# tester.net
KiCad netlist of a schematic drawn in EAGLE
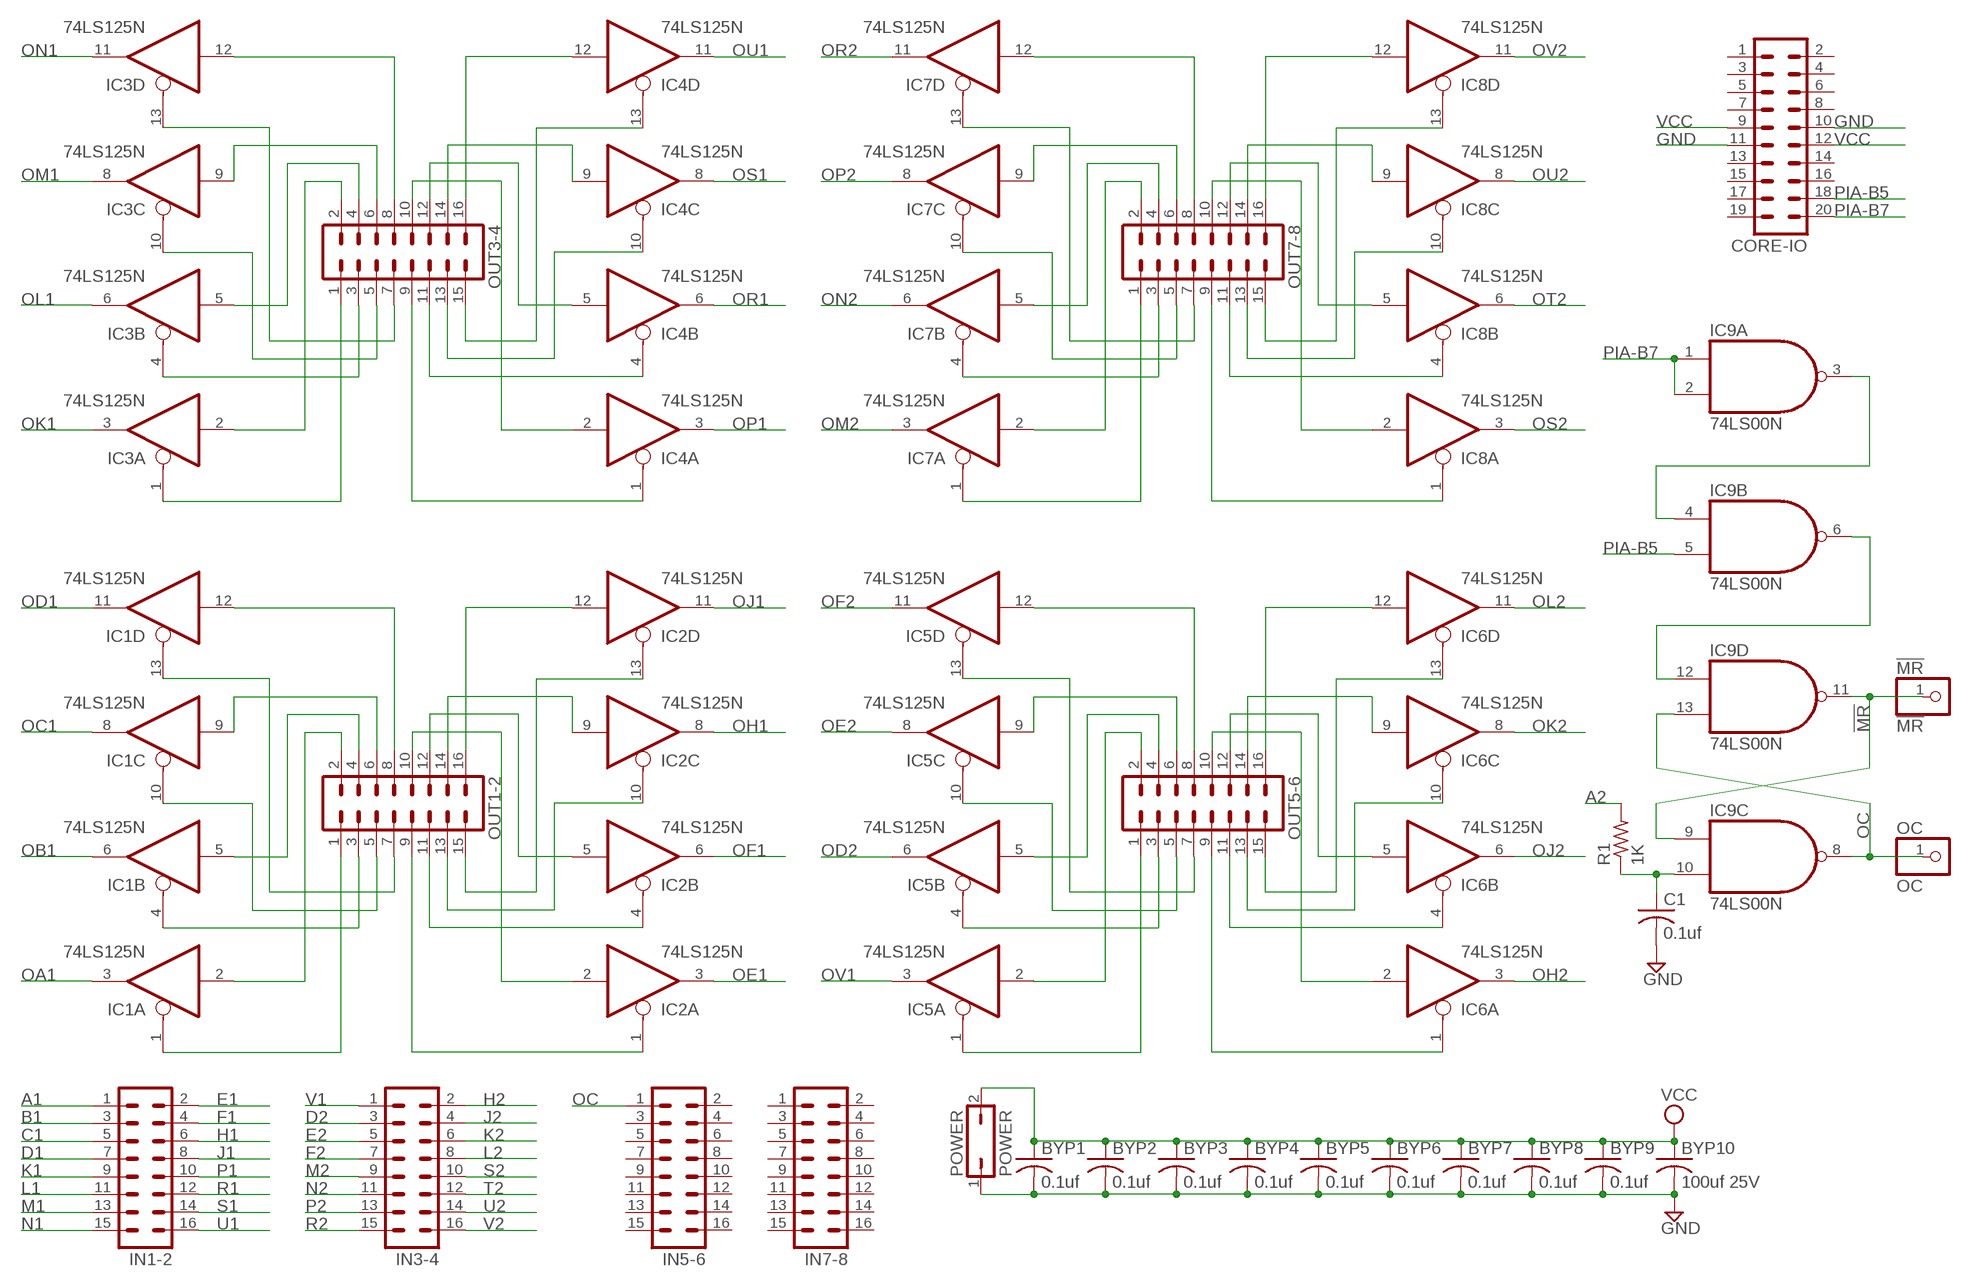
[diagram p0: schematic, sheet 1]
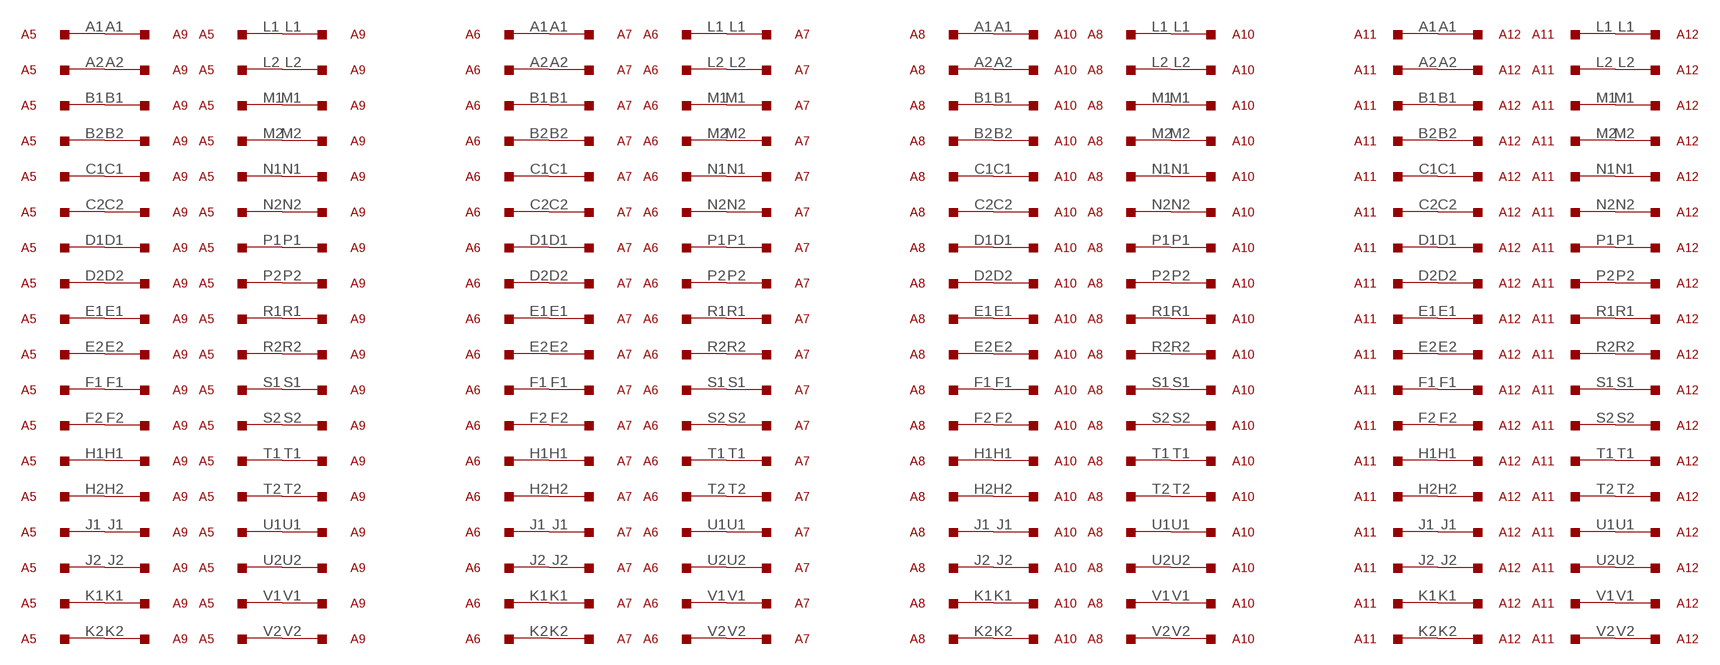
[diagram p1: schematic, sheet 2]
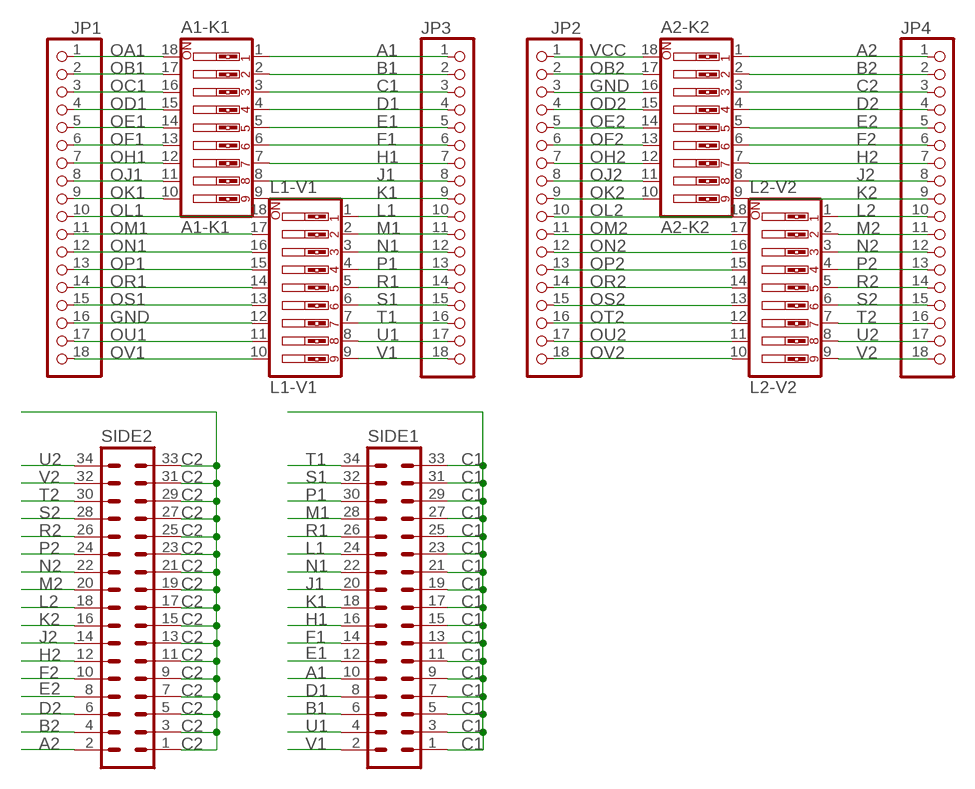
[diagram p2: schematic, sheet 3]

(export (version "E")
  (design (tool "Eeschema 10.0.6"))
  (components
    (comp (ref "A5")
      (value "M916")
      (footprint "eagle-import:H807")
      (libsource (lib "eagle-import") (part "M916"))
    )
    (comp (ref "A6")
      (value "M916")
      (footprint "eagle-import:H807")
      (libsource (lib "eagle-import") (part "M916"))
    )
    (comp (ref "A7")
      (value "M916")
      (footprint "eagle-import:H807")
      (libsource (lib "eagle-import") (part "M916"))
    )
    (comp (ref "A8")
      (value "M916")
      (footprint "eagle-import:H807")
      (libsource (lib "eagle-import") (part "M916"))
    )
    (comp (ref "A9")
      (value "M916")
      (footprint "eagle-import:H807")
      (libsource (lib "eagle-import") (part "M916"))
    )
    (comp (ref "A10")
      (value "M916")
      (footprint "eagle-import:H807")
      (libsource (lib "eagle-import") (part "M916"))
    )
    (comp (ref "A11")
      (value "M916")
      (footprint "eagle-import:H807")
      (libsource (lib "eagle-import") (part "M916"))
    )
    (comp (ref "A12")
      (value "M916")
      (footprint "eagle-import:H807")
      (libsource (lib "eagle-import") (part "M916"))
    )
    (comp (ref "!MR")
      (value "!MR")
      (footprint "eagle-import:1X01")
      (libsource (lib "eagle-import") (part "PINHD-1X1"))
    )
    (comp (ref "BYP1")
      (value "0.1uf")
      (footprint "eagle-import:C050-025X075")
      (libsource (lib "eagle-import") (part "C-US050-025X075"))
    )
    (comp (ref "BYP2")
      (value "0.1uf")
      (footprint "eagle-import:C050-025X075")
      (libsource (lib "eagle-import") (part "C-US050-025X075"))
    )
    (comp (ref "BYP3")
      (value "0.1uf")
      (footprint "eagle-import:C050-025X075")
      (libsource (lib "eagle-import") (part "C-US050-025X075"))
    )
    (comp (ref "BYP4")
      (value "0.1uf")
      (footprint "eagle-import:C050-025X075")
      (libsource (lib "eagle-import") (part "C-US050-025X075"))
    )
    (comp (ref "BYP5")
      (value "0.1uf")
      (footprint "eagle-import:C050-025X075")
      (libsource (lib "eagle-import") (part "C-US050-025X075"))
    )
    (comp (ref "BYP6")
      (value "0.1uf")
      (footprint "eagle-import:C050-025X075")
      (libsource (lib "eagle-import") (part "C-US050-025X075"))
    )
    (comp (ref "BYP7")
      (value "0.1uf")
      (footprint "eagle-import:C050-025X075")
      (libsource (lib "eagle-import") (part "C-US050-025X075"))
    )
    (comp (ref "BYP8")
      (value "0.1uf")
      (footprint "eagle-import:C050-025X075")
      (libsource (lib "eagle-import") (part "C-US050-025X075"))
    )
    (comp (ref "BYP9")
      (value "0.1uf")
      (footprint "eagle-import:C050-025X075")
      (libsource (lib "eagle-import") (part "C-US050-025X075"))
    )
    (comp (ref "BYP10")
      (value "100uf 25V")
      (footprint "eagle-import:C150-064X183")
      (libsource (lib "eagle-import") (part "C-US150-064X183"))
    )
    (comp (ref "C1")
      (value "0.1uf")
      (footprint "eagle-import:C050-025X075")
      (libsource (lib "eagle-import") (part "C-US050-025X075"))
    )
    (comp (ref "CORE-IO")
      (value "MA10-2")
      (footprint "eagle-import:MA10-2")
      (libsource (lib "eagle-import") (part "MA10-2"))
    )
    (comp (ref "IC1")
      (value "74LS125N")
      (footprint "eagle-import:DIL14")
      (libsource (lib "eagle-import") (part "74125NLS"))
    )
    (comp (ref "IC2")
      (value "74LS125N")
      (footprint "eagle-import:DIL14")
      (libsource (lib "eagle-import") (part "74125NLS"))
    )
    (comp (ref "IC3")
      (value "74LS125N")
      (footprint "eagle-import:DIL14")
      (libsource (lib "eagle-import") (part "74125NLS"))
    )
    (comp (ref "IC4")
      (value "74LS125N")
      (footprint "eagle-import:DIL14")
      (libsource (lib "eagle-import") (part "74125NLS"))
    )
    (comp (ref "IC5")
      (value "74LS125N")
      (footprint "eagle-import:DIL14")
      (libsource (lib "eagle-import") (part "74125NLS"))
    )
    (comp (ref "IC6")
      (value "74LS125N")
      (footprint "eagle-import:DIL14")
      (libsource (lib "eagle-import") (part "74125NLS"))
    )
    (comp (ref "IC7")
      (value "74LS125N")
      (footprint "eagle-import:DIL14")
      (libsource (lib "eagle-import") (part "74125NLS"))
    )
    (comp (ref "IC8")
      (value "74LS125N")
      (footprint "eagle-import:DIL14")
      (libsource (lib "eagle-import") (part "74125NLS"))
    )
    (comp (ref "IC9")
      (value "74LS00N")
      (footprint "eagle-import:DIL14")
      (libsource (lib "eagle-import") (part "7400NLS"))
    )
    (comp (ref "IN1-2")
      (value "MA08-2")
      (footprint "eagle-import:MA08-2")
      (libsource (lib "eagle-import") (part "MA08-2"))
    )
    (comp (ref "IN3-4")
      (value "MA08-2")
      (footprint "eagle-import:MA08-2")
      (libsource (lib "eagle-import") (part "MA08-2"))
    )
    (comp (ref "IN5-6")
      (value "MA08-2")
      (footprint "eagle-import:MA08-2")
      (libsource (lib "eagle-import") (part "MA08-2"))
    )
    (comp (ref "IN7-8")
      (value "MA08-2")
      (footprint "eagle-import:MA08-2")
      (libsource (lib "eagle-import") (part "MA08-2"))
    )
    (comp (ref "OC")
      (value "OC")
      (footprint "eagle-import:1X01")
      (libsource (lib "eagle-import") (part "PINHD-1X1"))
    )
    (comp (ref "OUT1-2")
      (value "MA08-2")
      (footprint "eagle-import:MA08-2")
      (libsource (lib "eagle-import") (part "MA08-2"))
    )
    (comp (ref "OUT3-4")
      (value "MA08-2")
      (footprint "eagle-import:MA08-2")
      (libsource (lib "eagle-import") (part "MA08-2"))
    )
    (comp (ref "OUT5-6")
      (value "MA08-2")
      (footprint "eagle-import:MA08-2")
      (libsource (lib "eagle-import") (part "MA08-2"))
    )
    (comp (ref "OUT7-8")
      (value "MA08-2")
      (footprint "eagle-import:MA08-2")
      (libsource (lib "eagle-import") (part "MA08-2"))
    )
    (comp (ref "POWER")
      (value "POWER")
      (footprint "eagle-import:JP1")
      (libsource (lib "eagle-import") (part "JP1Q"))
    )
    (comp (ref "R1")
      (value "1K")
      (footprint "eagle-import:0207_10")
      (libsource (lib "eagle-import") (part "R-US_0207/10"))
    )
    (comp (ref "A1-K1")
      (value "A1-K1")
      (footprint "eagle-import:EDG-09")
      (libsource (lib "eagle-import") (part "SW_DIP-9"))
    )
    (comp (ref "A2-K2")
      (value "A2-K2")
      (footprint "eagle-import:EDG-09")
      (libsource (lib "eagle-import") (part "SW_DIP-9"))
    )
    (comp (ref "JP1")
      (value "PINHD-1X18")
      (footprint "eagle-import:1X18")
      (libsource (lib "eagle-import") (part "PINHD-1X18"))
    )
    (comp (ref "JP2")
      (value "PINHD-1X18")
      (footprint "eagle-import:1X18")
      (libsource (lib "eagle-import") (part "PINHD-1X18"))
    )
    (comp (ref "JP3")
      (value "PINHD-1X18")
      (footprint "eagle-import:1X18")
      (libsource (lib "eagle-import") (part "PINHD-1X18"))
    )
    (comp (ref "JP4")
      (value "PINHD-1X18")
      (footprint "eagle-import:1X18")
      (libsource (lib "eagle-import") (part "PINHD-1X18"))
    )
    (comp (ref "L1-V1")
      (value "L1-V1")
      (footprint "eagle-import:EDG-09")
      (libsource (lib "eagle-import") (part "SW_DIP-9"))
    )
    (comp (ref "L2-V2")
      (value "L2-V2")
      (footprint "eagle-import:EDG-09")
      (libsource (lib "eagle-import") (part "SW_DIP-9"))
    )
    (comp (ref "SIDE1")
      (value "MA17-2")
      (footprint "eagle-import:MA17-2")
      (libsource (lib "eagle-import") (part "MA17-2"))
    )
    (comp (ref "SIDE2")
      (value "MA17-2")
      (footprint "eagle-import:MA17-2")
      (libsource (lib "eagle-import") (part "MA17-2"))
    )
  )
  (nets
    (net (code "1") (name "A1") (class "Default")
      (node (ref "A1-K1") (pin "1") (pinfunction "1_1") (pintype "passive"))
      (node (ref "IN1-2") (pin "1") (pinfunction "1_1") (pintype "passive"))
      (node (ref "JP3") (pin "1") (pinfunction "1_1") (pintype "passive"))
      (node (ref "SIDE1") (pin "10") (pinfunction "10_10") (pintype "passive"))
    )
    (net (code "2") (name "A2") (class "Default")
      (node (ref "A2-K2") (pin "1") (pinfunction "1_1") (pintype "passive"))
      (node (ref "JP4") (pin "1") (pinfunction "1_1") (pintype "passive"))
      (node (ref "R1") (pin "2") (pinfunction "2_2") (pintype "passive"))
      (node (ref "SIDE2") (pin "2") (pinfunction "2_2") (pintype "passive"))
    )
    (net (code "3") (name "B1") (class "Default")
      (node (ref "A1-K1") (pin "2") (pinfunction "2_2") (pintype "passive"))
      (node (ref "IN1-2") (pin "3") (pinfunction "3_3") (pintype "passive"))
      (node (ref "JP3") (pin "2") (pinfunction "2_2") (pintype "passive"))
      (node (ref "SIDE1") (pin "6") (pinfunction "6_6") (pintype "passive"))
    )
    (net (code "4") (name "B2") (class "Default")
      (node (ref "A2-K2") (pin "2") (pinfunction "2_2") (pintype "passive"))
      (node (ref "JP4") (pin "2") (pinfunction "2_2") (pintype "passive"))
      (node (ref "SIDE2") (pin "4") (pinfunction "4_4") (pintype "passive"))
    )
    (net (code "5") (name "C1") (class "Default")
      (node (ref "A1-K1") (pin "3") (pinfunction "3_3") (pintype "passive"))
      (node (ref "IN1-2") (pin "5") (pinfunction "5_5") (pintype "passive"))
      (node (ref "JP3") (pin "3") (pinfunction "3_3") (pintype "passive"))
      (node (ref "SIDE1") (pin "1") (pinfunction "1_1") (pintype "passive"))
      (node (ref "SIDE1") (pin "11") (pinfunction "11_11") (pintype "passive"))
      (node (ref "SIDE1") (pin "13") (pinfunction "13_13") (pintype "passive"))
      (node (ref "SIDE1") (pin "15") (pinfunction "15_15") (pintype "passive"))
      (node (ref "SIDE1") (pin "17") (pinfunction "17_17") (pintype "passive"))
      (node (ref "SIDE1") (pin "19") (pinfunction "19_19") (pintype "passive"))
      (node (ref "SIDE1") (pin "21") (pinfunction "21_21") (pintype "passive"))
      (node (ref "SIDE1") (pin "23") (pinfunction "23_23") (pintype "passive"))
      (node (ref "SIDE1") (pin "25") (pinfunction "25_25") (pintype "passive"))
      (node (ref "SIDE1") (pin "27") (pinfunction "27_27") (pintype "passive"))
      (node (ref "SIDE1") (pin "29") (pinfunction "29_29") (pintype "passive"))
      (node (ref "SIDE1") (pin "3") (pinfunction "3_3") (pintype "passive"))
      (node (ref "SIDE1") (pin "31") (pinfunction "31_31") (pintype "passive"))
      (node (ref "SIDE1") (pin "33") (pinfunction "33_33") (pintype "passive"))
      (node (ref "SIDE1") (pin "5") (pinfunction "5_5") (pintype "passive"))
      (node (ref "SIDE1") (pin "7") (pinfunction "7_7") (pintype "passive"))
      (node (ref "SIDE1") (pin "9") (pinfunction "9_9") (pintype "passive"))
    )
    (net (code "6") (name "C2") (class "Default")
      (node (ref "A2-K2") (pin "3") (pinfunction "3_3") (pintype "passive"))
      (node (ref "JP4") (pin "3") (pinfunction "3_3") (pintype "passive"))
      (node (ref "SIDE2") (pin "1") (pinfunction "1_1") (pintype "passive"))
      (node (ref "SIDE2") (pin "11") (pinfunction "11_11") (pintype "passive"))
      (node (ref "SIDE2") (pin "13") (pinfunction "13_13") (pintype "passive"))
      (node (ref "SIDE2") (pin "15") (pinfunction "15_15") (pintype "passive"))
      (node (ref "SIDE2") (pin "17") (pinfunction "17_17") (pintype "passive"))
      (node (ref "SIDE2") (pin "19") (pinfunction "19_19") (pintype "passive"))
      (node (ref "SIDE2") (pin "21") (pinfunction "21_21") (pintype "passive"))
      (node (ref "SIDE2") (pin "23") (pinfunction "23_23") (pintype "passive"))
      (node (ref "SIDE2") (pin "25") (pinfunction "25_25") (pintype "passive"))
      (node (ref "SIDE2") (pin "27") (pinfunction "27_27") (pintype "passive"))
      (node (ref "SIDE2") (pin "29") (pinfunction "29_29") (pintype "passive"))
      (node (ref "SIDE2") (pin "3") (pinfunction "3_3") (pintype "passive"))
      (node (ref "SIDE2") (pin "31") (pinfunction "31_31") (pintype "passive"))
      (node (ref "SIDE2") (pin "33") (pinfunction "33_33") (pintype "passive"))
      (node (ref "SIDE2") (pin "5") (pinfunction "5_5") (pintype "passive"))
      (node (ref "SIDE2") (pin "7") (pinfunction "7_7") (pintype "passive"))
      (node (ref "SIDE2") (pin "9") (pinfunction "9_9") (pintype "passive"))
    )
    (net (code "7") (name "D1") (class "Default")
      (node (ref "A1-K1") (pin "4") (pinfunction "4_4") (pintype "passive"))
      (node (ref "IN1-2") (pin "7") (pinfunction "7_7") (pintype "passive"))
      (node (ref "JP3") (pin "4") (pinfunction "4_4") (pintype "passive"))
      (node (ref "SIDE1") (pin "8") (pinfunction "8_8") (pintype "passive"))
    )
    (net (code "8") (name "D2") (class "Default")
      (node (ref "A2-K2") (pin "4") (pinfunction "4_4") (pintype "passive"))
      (node (ref "IN3-4") (pin "3") (pinfunction "3_3") (pintype "passive"))
      (node (ref "JP4") (pin "4") (pinfunction "4_4") (pintype "passive"))
      (node (ref "SIDE2") (pin "6") (pinfunction "6_6") (pintype "passive"))
    )
    (net (code "9") (name "E1") (class "Default")
      (node (ref "A1-K1") (pin "5") (pinfunction "5_5") (pintype "passive"))
      (node (ref "IN1-2") (pin "2") (pinfunction "2_2") (pintype "passive"))
      (node (ref "JP3") (pin "5") (pinfunction "5_5") (pintype "passive"))
      (node (ref "SIDE1") (pin "12") (pinfunction "12_12") (pintype "passive"))
    )
    (net (code "10") (name "E2") (class "Default")
      (node (ref "A2-K2") (pin "5") (pinfunction "5_5") (pintype "passive"))
      (node (ref "IN3-4") (pin "5") (pinfunction "5_5") (pintype "passive"))
      (node (ref "JP4") (pin "5") (pinfunction "5_5") (pintype "passive"))
      (node (ref "SIDE2") (pin "8") (pinfunction "8_8") (pintype "passive"))
    )
    (net (code "11") (name "F1") (class "Default")
      (node (ref "A1-K1") (pin "6") (pinfunction "6_6") (pintype "passive"))
      (node (ref "IN1-2") (pin "4") (pinfunction "4_4") (pintype "passive"))
      (node (ref "JP3") (pin "6") (pinfunction "6_6") (pintype "passive"))
      (node (ref "SIDE1") (pin "14") (pinfunction "14_14") (pintype "passive"))
    )
    (net (code "12") (name "F2") (class "Default")
      (node (ref "A2-K2") (pin "6") (pinfunction "6_6") (pintype "passive"))
      (node (ref "IN3-4") (pin "7") (pinfunction "7_7") (pintype "passive"))
      (node (ref "JP4") (pin "6") (pinfunction "6_6") (pintype "passive"))
      (node (ref "SIDE2") (pin "10") (pinfunction "10_10") (pintype "passive"))
    )
    (net (code "13") (name "GND") (class "Default")
      (node (ref "A2-K2") (pin "16") (pinfunction "16_16") (pintype "passive"))
      (node (ref "BYP1") (pin "2") (pinfunction "2_2") (pintype "passive"))
      (node (ref "BYP10") (pin "2") (pinfunction "2_2") (pintype "passive"))
      (node (ref "BYP2") (pin "2") (pinfunction "2_2") (pintype "passive"))
      (node (ref "BYP3") (pin "2") (pinfunction "2_2") (pintype "passive"))
      (node (ref "BYP4") (pin "2") (pinfunction "2_2") (pintype "passive"))
      (node (ref "BYP5") (pin "2") (pinfunction "2_2") (pintype "passive"))
      (node (ref "BYP6") (pin "2") (pinfunction "2_2") (pintype "passive"))
      (node (ref "BYP7") (pin "2") (pinfunction "2_2") (pintype "passive"))
      (node (ref "BYP8") (pin "2") (pinfunction "2_2") (pintype "passive"))
      (node (ref "BYP9") (pin "2") (pinfunction "2_2") (pintype "passive"))
      (node (ref "C1") (pin "2") (pinfunction "2_2") (pintype "passive"))
      (node (ref "CORE-IO") (pin "10") (pinfunction "10_10") (pintype "passive"))
      (node (ref "CORE-IO") (pin "11") (pinfunction "11_11") (pintype "passive"))
      (node (ref "JP1") (pin "16") (pinfunction "16_16") (pintype "passive"))
      (node (ref "JP2") (pin "3") (pinfunction "3_3") (pintype "passive"))
      (node (ref "L1-V1") (pin "12") (pinfunction "12_12") (pintype "passive"))
      (node (ref "POWER") (pin "1") (pinfunction "1_1") (pintype "passive"))
    )
    (net (code "14") (name "H1") (class "Default")
      (node (ref "A1-K1") (pin "7") (pinfunction "7_7") (pintype "passive"))
      (node (ref "IN1-2") (pin "6") (pinfunction "6_6") (pintype "passive"))
      (node (ref "JP3") (pin "7") (pinfunction "7_7") (pintype "passive"))
      (node (ref "SIDE1") (pin "16") (pinfunction "16_16") (pintype "passive"))
    )
    (net (code "15") (name "H2") (class "Default")
      (node (ref "A2-K2") (pin "7") (pinfunction "7_7") (pintype "passive"))
      (node (ref "IN3-4") (pin "2") (pinfunction "2_2") (pintype "passive"))
      (node (ref "JP4") (pin "7") (pinfunction "7_7") (pintype "passive"))
      (node (ref "SIDE2") (pin "12") (pinfunction "12_12") (pintype "passive"))
    )
    (net (code "16") (name "J1") (class "Default")
      (node (ref "A1-K1") (pin "8") (pinfunction "8_8") (pintype "passive"))
      (node (ref "IN1-2") (pin "8") (pinfunction "8_8") (pintype "passive"))
      (node (ref "JP3") (pin "8") (pinfunction "8_8") (pintype "passive"))
      (node (ref "SIDE1") (pin "20") (pinfunction "20_20") (pintype "passive"))
    )
    (net (code "17") (name "J2") (class "Default")
      (node (ref "A2-K2") (pin "8") (pinfunction "8_8") (pintype "passive"))
      (node (ref "IN3-4") (pin "4") (pinfunction "4_4") (pintype "passive"))
      (node (ref "JP4") (pin "8") (pinfunction "8_8") (pintype "passive"))
      (node (ref "SIDE2") (pin "14") (pinfunction "14_14") (pintype "passive"))
    )
    (net (code "18") (name "K1") (class "Default")
      (node (ref "A1-K1") (pin "9") (pinfunction "9_9") (pintype "passive"))
      (node (ref "IN1-2") (pin "9") (pinfunction "9_9") (pintype "passive"))
      (node (ref "JP3") (pin "9") (pinfunction "9_9") (pintype "passive"))
      (node (ref "SIDE1") (pin "18") (pinfunction "18_18") (pintype "passive"))
    )
    (net (code "19") (name "K2") (class "Default")
      (node (ref "A2-K2") (pin "9") (pinfunction "9_9") (pintype "passive"))
      (node (ref "IN3-4") (pin "6") (pinfunction "6_6") (pintype "passive"))
      (node (ref "JP4") (pin "9") (pinfunction "9_9") (pintype "passive"))
      (node (ref "SIDE2") (pin "16") (pinfunction "16_16") (pintype "passive"))
    )
    (net (code "20") (name "L1") (class "Default")
      (node (ref "IN1-2") (pin "11") (pinfunction "11_11") (pintype "passive"))
      (node (ref "JP3") (pin "10") (pinfunction "10_10") (pintype "passive"))
      (node (ref "L1-V1") (pin "1") (pinfunction "1_1") (pintype "passive"))
      (node (ref "SIDE1") (pin "24") (pinfunction "24_24") (pintype "passive"))
    )
    (net (code "21") (name "L2") (class "Default")
      (node (ref "IN3-4") (pin "8") (pinfunction "8_8") (pintype "passive"))
      (node (ref "JP4") (pin "10") (pinfunction "10_10") (pintype "passive"))
      (node (ref "L2-V2") (pin "1") (pinfunction "1_1") (pintype "passive"))
      (node (ref "SIDE2") (pin "18") (pinfunction "18_18") (pintype "passive"))
    )
    (net (code "22") (name "M1") (class "Default")
      (node (ref "IN1-2") (pin "13") (pinfunction "13_13") (pintype "passive"))
      (node (ref "JP3") (pin "11") (pinfunction "11_11") (pintype "passive"))
      (node (ref "L1-V1") (pin "2") (pinfunction "2_2") (pintype "passive"))
      (node (ref "SIDE1") (pin "28") (pinfunction "28_28") (pintype "passive"))
    )
    (net (code "23") (name "M2") (class "Default")
      (node (ref "IN3-4") (pin "9") (pinfunction "9_9") (pintype "passive"))
      (node (ref "JP4") (pin "11") (pinfunction "11_11") (pintype "passive"))
      (node (ref "L2-V2") (pin "2") (pinfunction "2_2") (pintype "passive"))
      (node (ref "SIDE2") (pin "20") (pinfunction "20_20") (pintype "passive"))
    )
    (net (code "24") (name "N1") (class "Default")
      (node (ref "IN1-2") (pin "15") (pinfunction "15_15") (pintype "passive"))
      (node (ref "JP3") (pin "12") (pinfunction "12_12") (pintype "passive"))
      (node (ref "L1-V1") (pin "3") (pinfunction "3_3") (pintype "passive"))
      (node (ref "SIDE1") (pin "22") (pinfunction "22_22") (pintype "passive"))
    )
    (net (code "25") (name "N2") (class "Default")
      (node (ref "IN3-4") (pin "11") (pinfunction "11_11") (pintype "passive"))
      (node (ref "JP4") (pin "12") (pinfunction "12_12") (pintype "passive"))
      (node (ref "L2-V2") (pin "3") (pinfunction "3_3") (pintype "passive"))
      (node (ref "SIDE2") (pin "22") (pinfunction "22_22") (pintype "passive"))
    )
    (net (code "26") (name "Net-(A5A-P$2)") (class "Default")
      (node (ref "A5") (pin "A1") (pinfunction "P$2_A1") (pintype "bidirectional"))
      (node (ref "A9") (pin "A1") (pinfunction "P$2_A1") (pintype "bidirectional"))
    )
    (net (code "27") (name "Net-(A5AA-P$2)") (class "Default")
      (node (ref "A5") (pin "R1") (pinfunction "P$2_R1") (pintype "bidirectional"))
      (node (ref "A9") (pin "R1") (pinfunction "P$2_R1") (pintype "bidirectional"))
    )
    (net (code "28") (name "Net-(A5AB-P$2)") (class "Default")
      (node (ref "A5") (pin "R2") (pinfunction "P$2_R2") (pintype "bidirectional"))
      (node (ref "A9") (pin "R2") (pinfunction "P$2_R2") (pintype "bidirectional"))
    )
    (net (code "29") (name "Net-(A5AC-P$2)") (class "Default")
      (node (ref "A5") (pin "S1") (pinfunction "P$2_S1") (pintype "bidirectional"))
      (node (ref "A9") (pin "S1") (pinfunction "P$2_S1") (pintype "bidirectional"))
    )
    (net (code "30") (name "Net-(A5AD-P$2)") (class "Default")
      (node (ref "A5") (pin "S2") (pinfunction "P$2_S2") (pintype "bidirectional"))
      (node (ref "A9") (pin "S2") (pinfunction "P$2_S2") (pintype "bidirectional"))
    )
    (net (code "31") (name "Net-(A5AE-P$2)") (class "Default")
      (node (ref "A5") (pin "T1") (pinfunction "P$2_T1") (pintype "bidirectional"))
      (node (ref "A9") (pin "T1") (pinfunction "P$2_T1") (pintype "bidirectional"))
    )
    (net (code "32") (name "Net-(A5AF-P$2)") (class "Default")
      (node (ref "A5") (pin "T2") (pinfunction "P$2_T2") (pintype "bidirectional"))
      (node (ref "A9") (pin "T2") (pinfunction "P$2_T2") (pintype "bidirectional"))
    )
    (net (code "33") (name "Net-(A5AG-P$2)") (class "Default")
      (node (ref "A5") (pin "U1") (pinfunction "P$2_U1") (pintype "bidirectional"))
      (node (ref "A9") (pin "U1") (pinfunction "P$2_U1") (pintype "bidirectional"))
    )
    (net (code "34") (name "Net-(A5AH-P$2)") (class "Default")
      (node (ref "A5") (pin "U2") (pinfunction "P$2_U2") (pintype "bidirectional"))
      (node (ref "A9") (pin "U2") (pinfunction "P$2_U2") (pintype "bidirectional"))
    )
    (net (code "35") (name "Net-(A5AI-P$2)") (class "Default")
      (node (ref "A5") (pin "V1") (pinfunction "P$2_V1") (pintype "bidirectional"))
      (node (ref "A9") (pin "V1") (pinfunction "P$2_V1") (pintype "bidirectional"))
    )
    (net (code "36") (name "Net-(A5AJ-P$2)") (class "Default")
      (node (ref "A5") (pin "V2") (pinfunction "P$2_V2") (pintype "bidirectional"))
      (node (ref "A9") (pin "V2") (pinfunction "P$2_V2") (pintype "bidirectional"))
    )
    (net (code "37") (name "Net-(A5B-P$2)") (class "Default")
      (node (ref "A5") (pin "A2") (pinfunction "P$2_A2") (pintype "bidirectional"))
      (node (ref "A9") (pin "A2") (pinfunction "P$2_A2") (pintype "bidirectional"))
    )
    (net (code "38") (name "Net-(A5C-P$2)") (class "Default")
      (node (ref "A5") (pin "B1") (pinfunction "P$2_B1") (pintype "bidirectional"))
      (node (ref "A9") (pin "B1") (pinfunction "P$2_B1") (pintype "bidirectional"))
    )
    (net (code "39") (name "Net-(A5D-P$2)") (class "Default")
      (node (ref "A5") (pin "B2") (pinfunction "P$2_B2") (pintype "bidirectional"))
      (node (ref "A9") (pin "B2") (pinfunction "P$2_B2") (pintype "bidirectional"))
    )
    (net (code "40") (name "Net-(A5E-P$2)") (class "Default")
      (node (ref "A5") (pin "C1") (pinfunction "P$2_C1") (pintype "bidirectional"))
      (node (ref "A9") (pin "C1") (pinfunction "P$2_C1") (pintype "bidirectional"))
    )
    (net (code "41") (name "Net-(A5F-P$2)") (class "Default")
      (node (ref "A5") (pin "C2") (pinfunction "P$2_C2") (pintype "bidirectional"))
      (node (ref "A9") (pin "C2") (pinfunction "P$2_C2") (pintype "bidirectional"))
    )
    (net (code "42") (name "Net-(A5G-P$2)") (class "Default")
      (node (ref "A5") (pin "D1") (pinfunction "P$2_D1") (pintype "bidirectional"))
      (node (ref "A9") (pin "D1") (pinfunction "P$2_D1") (pintype "bidirectional"))
    )
    (net (code "43") (name "Net-(A5H-P$2)") (class "Default")
      (node (ref "A5") (pin "D2") (pinfunction "P$2_D2") (pintype "bidirectional"))
      (node (ref "A9") (pin "D2") (pinfunction "P$2_D2") (pintype "bidirectional"))
    )
    (net (code "44") (name "Net-(A5I-P$2)") (class "Default")
      (node (ref "A5") (pin "E1") (pinfunction "P$2_E1") (pintype "bidirectional"))
      (node (ref "A9") (pin "E1") (pinfunction "P$2_E1") (pintype "bidirectional"))
    )
    (net (code "45") (name "Net-(A5J-P$2)") (class "Default")
      (node (ref "A5") (pin "E2") (pinfunction "P$2_E2") (pintype "bidirectional"))
      (node (ref "A9") (pin "E2") (pinfunction "P$2_E2") (pintype "bidirectional"))
    )
    (net (code "46") (name "Net-(A5K-P$2)") (class "Default")
      (node (ref "A5") (pin "F1") (pinfunction "P$2_F1") (pintype "bidirectional"))
      (node (ref "A9") (pin "F1") (pinfunction "P$2_F1") (pintype "bidirectional"))
    )
    (net (code "47") (name "Net-(A5L-P$2)") (class "Default")
      (node (ref "A5") (pin "F2") (pinfunction "P$2_F2") (pintype "bidirectional"))
      (node (ref "A9") (pin "F2") (pinfunction "P$2_F2") (pintype "bidirectional"))
    )
    (net (code "48") (name "Net-(A5M-P$2)") (class "Default")
      (node (ref "A5") (pin "H1") (pinfunction "P$2_H1") (pintype "bidirectional"))
      (node (ref "A9") (pin "H1") (pinfunction "P$2_H1") (pintype "bidirectional"))
    )
    (net (code "49") (name "Net-(A5N-P$2)") (class "Default")
      (node (ref "A5") (pin "H2") (pinfunction "P$2_H2") (pintype "bidirectional"))
      (node (ref "A9") (pin "H2") (pinfunction "P$2_H2") (pintype "bidirectional"))
    )
    (net (code "50") (name "Net-(A5O-P$2)") (class "Default")
      (node (ref "A5") (pin "J1") (pinfunction "P$2_J1") (pintype "bidirectional"))
      (node (ref "A9") (pin "J1") (pinfunction "P$2_J1") (pintype "bidirectional"))
    )
    (net (code "51") (name "Net-(A5P-P$2)") (class "Default")
      (node (ref "A5") (pin "J2") (pinfunction "P$2_J2") (pintype "bidirectional"))
      (node (ref "A9") (pin "J2") (pinfunction "P$2_J2") (pintype "bidirectional"))
    )
    (net (code "52") (name "Net-(A5Q-P$2)") (class "Default")
      (node (ref "A5") (pin "K1") (pinfunction "P$2_K1") (pintype "bidirectional"))
      (node (ref "A9") (pin "K1") (pinfunction "P$2_K1") (pintype "bidirectional"))
    )
    (net (code "53") (name "Net-(A5R-P$2)") (class "Default")
      (node (ref "A5") (pin "K2") (pinfunction "P$2_K2") (pintype "bidirectional"))
      (node (ref "A9") (pin "K2") (pinfunction "P$2_K2") (pintype "bidirectional"))
    )
    (net (code "54") (name "Net-(A5S-P$2)") (class "Default")
      (node (ref "A5") (pin "L1") (pinfunction "P$2_L1") (pintype "bidirectional"))
      (node (ref "A9") (pin "L1") (pinfunction "P$2_L1") (pintype "bidirectional"))
    )
    (net (code "55") (name "Net-(A5T-P$2)") (class "Default")
      (node (ref "A5") (pin "L2") (pinfunction "P$2_L2") (pintype "bidirectional"))
      (node (ref "A9") (pin "L2") (pinfunction "P$2_L2") (pintype "bidirectional"))
    )
    (net (code "56") (name "Net-(A5U-P$2)") (class "Default")
      (node (ref "A5") (pin "M1") (pinfunction "P$2_M1") (pintype "bidirectional"))
      (node (ref "A9") (pin "M1") (pinfunction "P$2_M1") (pintype "bidirectional"))
    )
    (net (code "57") (name "Net-(A5V-P$2)") (class "Default")
      (node (ref "A5") (pin "M2") (pinfunction "P$2_M2") (pintype "bidirectional"))
      (node (ref "A9") (pin "M2") (pinfunction "P$2_M2") (pintype "bidirectional"))
    )
    (net (code "58") (name "Net-(A5W-P$2)") (class "Default")
      (node (ref "A5") (pin "N1") (pinfunction "P$2_N1") (pintype "bidirectional"))
      (node (ref "A9") (pin "N1") (pinfunction "P$2_N1") (pintype "bidirectional"))
    )
    (net (code "59") (name "Net-(A5X-P$2)") (class "Default")
      (node (ref "A5") (pin "N2") (pinfunction "P$2_N2") (pintype "bidirectional"))
      (node (ref "A9") (pin "N2") (pinfunction "P$2_N2") (pintype "bidirectional"))
    )
    (net (code "60") (name "Net-(A5Y-P$2)") (class "Default")
      (node (ref "A5") (pin "P1") (pinfunction "P$2_P1") (pintype "bidirectional"))
      (node (ref "A9") (pin "P1") (pinfunction "P$2_P1") (pintype "bidirectional"))
    )
    (net (code "61") (name "Net-(A5Z-P$2)") (class "Default")
      (node (ref "A5") (pin "P2") (pinfunction "P$2_P2") (pintype "bidirectional"))
      (node (ref "A9") (pin "P2") (pinfunction "P$2_P2") (pintype "bidirectional"))
    )
    (net (code "62") (name "Net-(A6A-P$2)") (class "Default")
      (node (ref "A6") (pin "A1") (pinfunction "P$2_A1") (pintype "bidirectional"))
      (node (ref "A7") (pin "A1") (pinfunction "P$2_A1") (pintype "bidirectional"))
    )
    (net (code "63") (name "Net-(A6AA-P$2)") (class "Default")
      (node (ref "A6") (pin "R1") (pinfunction "P$2_R1") (pintype "bidirectional"))
      (node (ref "A7") (pin "R1") (pinfunction "P$2_R1") (pintype "bidirectional"))
    )
    (net (code "64") (name "Net-(A6AB-P$2)") (class "Default")
      (node (ref "A6") (pin "R2") (pinfunction "P$2_R2") (pintype "bidirectional"))
      (node (ref "A7") (pin "R2") (pinfunction "P$2_R2") (pintype "bidirectional"))
    )
    (net (code "65") (name "Net-(A6AC-P$2)") (class "Default")
      (node (ref "A6") (pin "S1") (pinfunction "P$2_S1") (pintype "bidirectional"))
      (node (ref "A7") (pin "S1") (pinfunction "P$2_S1") (pintype "bidirectional"))
    )
    (net (code "66") (name "Net-(A6AD-P$2)") (class "Default")
      (node (ref "A6") (pin "S2") (pinfunction "P$2_S2") (pintype "bidirectional"))
      (node (ref "A7") (pin "S2") (pinfunction "P$2_S2") (pintype "bidirectional"))
    )
    (net (code "67") (name "Net-(A6AE-P$2)") (class "Default")
      (node (ref "A6") (pin "T1") (pinfunction "P$2_T1") (pintype "bidirectional"))
      (node (ref "A7") (pin "T1") (pinfunction "P$2_T1") (pintype "bidirectional"))
    )
    (net (code "68") (name "Net-(A6AF-P$2)") (class "Default")
      (node (ref "A6") (pin "T2") (pinfunction "P$2_T2") (pintype "bidirectional"))
      (node (ref "A7") (pin "T2") (pinfunction "P$2_T2") (pintype "bidirectional"))
    )
    (net (code "69") (name "Net-(A6AG-P$2)") (class "Default")
      (node (ref "A6") (pin "U1") (pinfunction "P$2_U1") (pintype "bidirectional"))
      (node (ref "A7") (pin "U1") (pinfunction "P$2_U1") (pintype "bidirectional"))
    )
    (net (code "70") (name "Net-(A6AH-P$2)") (class "Default")
      (node (ref "A6") (pin "U2") (pinfunction "P$2_U2") (pintype "bidirectional"))
      (node (ref "A7") (pin "U2") (pinfunction "P$2_U2") (pintype "bidirectional"))
    )
    (net (code "71") (name "Net-(A6AI-P$2)") (class "Default")
      (node (ref "A6") (pin "V1") (pinfunction "P$2_V1") (pintype "bidirectional"))
      (node (ref "A7") (pin "V1") (pinfunction "P$2_V1") (pintype "bidirectional"))
    )
    (net (code "72") (name "Net-(A6AJ-P$2)") (class "Default")
      (node (ref "A6") (pin "V2") (pinfunction "P$2_V2") (pintype "bidirectional"))
      (node (ref "A7") (pin "V2") (pinfunction "P$2_V2") (pintype "bidirectional"))
    )
    (net (code "73") (name "Net-(A6B-P$2)") (class "Default")
      (node (ref "A6") (pin "A2") (pinfunction "P$2_A2") (pintype "bidirectional"))
      (node (ref "A7") (pin "A2") (pinfunction "P$2_A2") (pintype "bidirectional"))
    )
    (net (code "74") (name "Net-(A6C-P$2)") (class "Default")
      (node (ref "A6") (pin "B1") (pinfunction "P$2_B1") (pintype "bidirectional"))
      (node (ref "A7") (pin "B1") (pinfunction "P$2_B1") (pintype "bidirectional"))
    )
    (net (code "75") (name "Net-(A6D-P$2)") (class "Default")
      (node (ref "A6") (pin "B2") (pinfunction "P$2_B2") (pintype "bidirectional"))
      (node (ref "A7") (pin "B2") (pinfunction "P$2_B2") (pintype "bidirectional"))
    )
    (net (code "76") (name "Net-(A6E-P$2)") (class "Default")
      (node (ref "A6") (pin "C1") (pinfunction "P$2_C1") (pintype "bidirectional"))
      (node (ref "A7") (pin "C1") (pinfunction "P$2_C1") (pintype "bidirectional"))
    )
    (net (code "77") (name "Net-(A6F-P$2)") (class "Default")
      (node (ref "A6") (pin "C2") (pinfunction "P$2_C2") (pintype "bidirectional"))
      (node (ref "A7") (pin "C2") (pinfunction "P$2_C2") (pintype "bidirectional"))
    )
    (net (code "78") (name "Net-(A6G-P$2)") (class "Default")
      (node (ref "A6") (pin "D1") (pinfunction "P$2_D1") (pintype "bidirectional"))
      (node (ref "A7") (pin "D1") (pinfunction "P$2_D1") (pintype "bidirectional"))
    )
    (net (code "79") (name "Net-(A6H-P$2)") (class "Default")
      (node (ref "A6") (pin "D2") (pinfunction "P$2_D2") (pintype "bidirectional"))
      (node (ref "A7") (pin "D2") (pinfunction "P$2_D2") (pintype "bidirectional"))
    )
    (net (code "80") (name "Net-(A6I-P$2)") (class "Default")
      (node (ref "A6") (pin "E1") (pinfunction "P$2_E1") (pintype "bidirectional"))
      (node (ref "A7") (pin "E1") (pinfunction "P$2_E1") (pintype "bidirectional"))
    )
    (net (code "81") (name "Net-(A6J-P$2)") (class "Default")
      (node (ref "A6") (pin "E2") (pinfunction "P$2_E2") (pintype "bidirectional"))
      (node (ref "A7") (pin "E2") (pinfunction "P$2_E2") (pintype "bidirectional"))
    )
    (net (code "82") (name "Net-(A6K-P$2)") (class "Default")
      (node (ref "A6") (pin "F1") (pinfunction "P$2_F1") (pintype "bidirectional"))
      (node (ref "A7") (pin "F1") (pinfunction "P$2_F1") (pintype "bidirectional"))
    )
    (net (code "83") (name "Net-(A6L-P$2)") (class "Default")
      (node (ref "A6") (pin "F2") (pinfunction "P$2_F2") (pintype "bidirectional"))
      (node (ref "A7") (pin "F2") (pinfunction "P$2_F2") (pintype "bidirectional"))
    )
    (net (code "84") (name "Net-(A6M-P$2)") (class "Default")
      (node (ref "A6") (pin "H1") (pinfunction "P$2_H1") (pintype "bidirectional"))
      (node (ref "A7") (pin "H1") (pinfunction "P$2_H1") (pintype "bidirectional"))
    )
    (net (code "85") (name "Net-(A6N-P$2)") (class "Default")
      (node (ref "A6") (pin "H2") (pinfunction "P$2_H2") (pintype "bidirectional"))
      (node (ref "A7") (pin "H2") (pinfunction "P$2_H2") (pintype "bidirectional"))
    )
    (net (code "86") (name "Net-(A6O-P$2)") (class "Default")
      (node (ref "A6") (pin "J1") (pinfunction "P$2_J1") (pintype "bidirectional"))
      (node (ref "A7") (pin "J1") (pinfunction "P$2_J1") (pintype "bidirectional"))
    )
    (net (code "87") (name "Net-(A6P-P$2)") (class "Default")
      (node (ref "A6") (pin "J2") (pinfunction "P$2_J2") (pintype "bidirectional"))
      (node (ref "A7") (pin "J2") (pinfunction "P$2_J2") (pintype "bidirectional"))
    )
    (net (code "88") (name "Net-(A6Q-P$2)") (class "Default")
      (node (ref "A6") (pin "K1") (pinfunction "P$2_K1") (pintype "bidirectional"))
      (node (ref "A7") (pin "K1") (pinfunction "P$2_K1") (pintype "bidirectional"))
    )
    (net (code "89") (name "Net-(A6R-P$2)") (class "Default")
      (node (ref "A6") (pin "K2") (pinfunction "P$2_K2") (pintype "bidirectional"))
      (node (ref "A7") (pin "K2") (pinfunction "P$2_K2") (pintype "bidirectional"))
    )
    (net (code "90") (name "Net-(A6S-P$2)") (class "Default")
      (node (ref "A6") (pin "L1") (pinfunction "P$2_L1") (pintype "bidirectional"))
      (node (ref "A7") (pin "L1") (pinfunction "P$2_L1") (pintype "bidirectional"))
    )
    (net (code "91") (name "Net-(A6T-P$2)") (class "Default")
      (node (ref "A6") (pin "L2") (pinfunction "P$2_L2") (pintype "bidirectional"))
      (node (ref "A7") (pin "L2") (pinfunction "P$2_L2") (pintype "bidirectional"))
    )
    (net (code "92") (name "Net-(A6U-P$2)") (class "Default")
      (node (ref "A6") (pin "M1") (pinfunction "P$2_M1") (pintype "bidirectional"))
      (node (ref "A7") (pin "M1") (pinfunction "P$2_M1") (pintype "bidirectional"))
    )
    (net (code "93") (name "Net-(A6V-P$2)") (class "Default")
      (node (ref "A6") (pin "M2") (pinfunction "P$2_M2") (pintype "bidirectional"))
      (node (ref "A7") (pin "M2") (pinfunction "P$2_M2") (pintype "bidirectional"))
    )
    (net (code "94") (name "Net-(A6W-P$2)") (class "Default")
      (node (ref "A6") (pin "N1") (pinfunction "P$2_N1") (pintype "bidirectional"))
      (node (ref "A7") (pin "N1") (pinfunction "P$2_N1") (pintype "bidirectional"))
    )
    (net (code "95") (name "Net-(A6X-P$2)") (class "Default")
      (node (ref "A6") (pin "N2") (pinfunction "P$2_N2") (pintype "bidirectional"))
      (node (ref "A7") (pin "N2") (pinfunction "P$2_N2") (pintype "bidirectional"))
    )
    (net (code "96") (name "Net-(A6Y-P$2)") (class "Default")
      (node (ref "A6") (pin "P1") (pinfunction "P$2_P1") (pintype "bidirectional"))
      (node (ref "A7") (pin "P1") (pinfunction "P$2_P1") (pintype "bidirectional"))
    )
    (net (code "97") (name "Net-(A6Z-P$2)") (class "Default")
      (node (ref "A6") (pin "P2") (pinfunction "P$2_P2") (pintype "bidirectional"))
      (node (ref "A7") (pin "P2") (pinfunction "P$2_P2") (pintype "bidirectional"))
    )
    (net (code "98") (name "Net-(A10A-P$2)") (class "Default")
      (node (ref "A10") (pin "A1") (pinfunction "P$2_A1") (pintype "bidirectional"))
      (node (ref "A8") (pin "A1") (pinfunction "P$2_A1") (pintype "bidirectional"))
    )
    (net (code "99") (name "Net-(A10AA-P$2)") (class "Default")
      (node (ref "A10") (pin "R1") (pinfunction "P$2_R1") (pintype "bidirectional"))
      (node (ref "A8") (pin "R1") (pinfunction "P$2_R1") (pintype "bidirectional"))
    )
    (net (code "100") (name "Net-(A10AB-P$2)") (class "Default")
      (node (ref "A10") (pin "R2") (pinfunction "P$2_R2") (pintype "bidirectional"))
      (node (ref "A8") (pin "R2") (pinfunction "P$2_R2") (pintype "bidirectional"))
    )
    (net (code "101") (name "Net-(A10AC-P$2)") (class "Default")
      (node (ref "A10") (pin "S1") (pinfunction "P$2_S1") (pintype "bidirectional"))
      (node (ref "A8") (pin "S1") (pinfunction "P$2_S1") (pintype "bidirectional"))
    )
    (net (code "102") (name "Net-(A10AD-P$2)") (class "Default")
      (node (ref "A10") (pin "S2") (pinfunction "P$2_S2") (pintype "bidirectional"))
      (node (ref "A8") (pin "S2") (pinfunction "P$2_S2") (pintype "bidirectional"))
    )
    (net (code "103") (name "Net-(A10AE-P$2)") (class "Default")
      (node (ref "A10") (pin "T1") (pinfunction "P$2_T1") (pintype "bidirectional"))
      (node (ref "A8") (pin "T1") (pinfunction "P$2_T1") (pintype "bidirectional"))
    )
    (net (code "104") (name "Net-(A10AF-P$2)") (class "Default")
      (node (ref "A10") (pin "T2") (pinfunction "P$2_T2") (pintype "bidirectional"))
      (node (ref "A8") (pin "T2") (pinfunction "P$2_T2") (pintype "bidirectional"))
    )
    (net (code "105") (name "Net-(A10AG-P$2)") (class "Default")
      (node (ref "A10") (pin "U1") (pinfunction "P$2_U1") (pintype "bidirectional"))
      (node (ref "A8") (pin "U1") (pinfunction "P$2_U1") (pintype "bidirectional"))
    )
    (net (code "106") (name "Net-(A10AH-P$2)") (class "Default")
      (node (ref "A10") (pin "U2") (pinfunction "P$2_U2") (pintype "bidirectional"))
      (node (ref "A8") (pin "U2") (pinfunction "P$2_U2") (pintype "bidirectional"))
    )
    (net (code "107") (name "Net-(A10AI-P$2)") (class "Default")
      (node (ref "A10") (pin "V1") (pinfunction "P$2_V1") (pintype "bidirectional"))
      (node (ref "A8") (pin "V1") (pinfunction "P$2_V1") (pintype "bidirectional"))
    )
    (net (code "108") (name "Net-(A10AJ-P$2)") (class "Default")
      (node (ref "A10") (pin "V2") (pinfunction "P$2_V2") (pintype "bidirectional"))
      (node (ref "A8") (pin "V2") (pinfunction "P$2_V2") (pintype "bidirectional"))
    )
    (net (code "109") (name "Net-(A10B-P$2)") (class "Default")
      (node (ref "A10") (pin "A2") (pinfunction "P$2_A2") (pintype "bidirectional"))
      (node (ref "A8") (pin "A2") (pinfunction "P$2_A2") (pintype "bidirectional"))
    )
    (net (code "110") (name "Net-(A10C-P$2)") (class "Default")
      (node (ref "A10") (pin "B1") (pinfunction "P$2_B1") (pintype "bidirectional"))
      (node (ref "A8") (pin "B1") (pinfunction "P$2_B1") (pintype "bidirectional"))
    )
    (net (code "111") (name "Net-(A10D-P$2)") (class "Default")
      (node (ref "A10") (pin "B2") (pinfunction "P$2_B2") (pintype "bidirectional"))
      (node (ref "A8") (pin "B2") (pinfunction "P$2_B2") (pintype "bidirectional"))
    )
    (net (code "112") (name "Net-(A10E-P$2)") (class "Default")
      (node (ref "A10") (pin "C1") (pinfunction "P$2_C1") (pintype "bidirectional"))
      (node (ref "A8") (pin "C1") (pinfunction "P$2_C1") (pintype "bidirectional"))
    )
    (net (code "113") (name "Net-(A10F-P$2)") (class "Default")
      (node (ref "A10") (pin "C2") (pinfunction "P$2_C2") (pintype "bidirectional"))
      (node (ref "A8") (pin "C2") (pinfunction "P$2_C2") (pintype "bidirectional"))
    )
    (net (code "114") (name "Net-(A10G-P$2)") (class "Default")
      (node (ref "A10") (pin "D1") (pinfunction "P$2_D1") (pintype "bidirectional"))
      (node (ref "A8") (pin "D1") (pinfunction "P$2_D1") (pintype "bidirectional"))
    )
    (net (code "115") (name "Net-(A10H-P$2)") (class "Default")
      (node (ref "A10") (pin "D2") (pinfunction "P$2_D2") (pintype "bidirectional"))
      (node (ref "A8") (pin "D2") (pinfunction "P$2_D2") (pintype "bidirectional"))
    )
    (net (code "116") (name "Net-(A10I-P$2)") (class "Default")
      (node (ref "A10") (pin "E1") (pinfunction "P$2_E1") (pintype "bidirectional"))
      (node (ref "A8") (pin "E1") (pinfunction "P$2_E1") (pintype "bidirectional"))
    )
    (net (code "117") (name "Net-(A10J-P$2)") (class "Default")
      (node (ref "A10") (pin "E2") (pinfunction "P$2_E2") (pintype "bidirectional"))
      (node (ref "A8") (pin "E2") (pinfunction "P$2_E2") (pintype "bidirectional"))
    )
    (net (code "118") (name "Net-(A10K-P$2)") (class "Default")
      (node (ref "A10") (pin "F1") (pinfunction "P$2_F1") (pintype "bidirectional"))
      (node (ref "A8") (pin "F1") (pinfunction "P$2_F1") (pintype "bidirectional"))
    )
    (net (code "119") (name "Net-(A10L-P$2)") (class "Default")
      (node (ref "A10") (pin "F2") (pinfunction "P$2_F2") (pintype "bidirectional"))
      (node (ref "A8") (pin "F2") (pinfunction "P$2_F2") (pintype "bidirectional"))
    )
    (net (code "120") (name "Net-(A10M-P$2)") (class "Default")
      (node (ref "A10") (pin "H1") (pinfunction "P$2_H1") (pintype "bidirectional"))
      (node (ref "A8") (pin "H1") (pinfunction "P$2_H1") (pintype "bidirectional"))
    )
    (net (code "121") (name "Net-(A10N-P$2)") (class "Default")
      (node (ref "A10") (pin "H2") (pinfunction "P$2_H2") (pintype "bidirectional"))
      (node (ref "A8") (pin "H2") (pinfunction "P$2_H2") (pintype "bidirectional"))
    )
    (net (code "122") (name "Net-(A10O-P$2)") (class "Default")
      (node (ref "A10") (pin "J1") (pinfunction "P$2_J1") (pintype "bidirectional"))
      (node (ref "A8") (pin "J1") (pinfunction "P$2_J1") (pintype "bidirectional"))
    )
    (net (code "123") (name "Net-(A10P-P$2)") (class "Default")
      (node (ref "A10") (pin "J2") (pinfunction "P$2_J2") (pintype "bidirectional"))
      (node (ref "A8") (pin "J2") (pinfunction "P$2_J2") (pintype "bidirectional"))
    )
    (net (code "124") (name "Net-(A10Q-P$2)") (class "Default")
      (node (ref "A10") (pin "K1") (pinfunction "P$2_K1") (pintype "bidirectional"))
      (node (ref "A8") (pin "K1") (pinfunction "P$2_K1") (pintype "bidirectional"))
    )
    (net (code "125") (name "Net-(A10R-P$2)") (class "Default")
      (node (ref "A10") (pin "K2") (pinfunction "P$2_K2") (pintype "bidirectional"))
      (node (ref "A8") (pin "K2") (pinfunction "P$2_K2") (pintype "bidirectional"))
    )
    (net (code "126") (name "Net-(A10S-P$2)") (class "Default")
      (node (ref "A10") (pin "L1") (pinfunction "P$2_L1") (pintype "bidirectional"))
      (node (ref "A8") (pin "L1") (pinfunction "P$2_L1") (pintype "bidirectional"))
    )
    (net (code "127") (name "Net-(A10T-P$2)") (class "Default")
      (node (ref "A10") (pin "L2") (pinfunction "P$2_L2") (pintype "bidirectional"))
      (node (ref "A8") (pin "L2") (pinfunction "P$2_L2") (pintype "bidirectional"))
    )
    (net (code "128") (name "Net-(A10U-P$2)") (class "Default")
      (node (ref "A10") (pin "M1") (pinfunction "P$2_M1") (pintype "bidirectional"))
      (node (ref "A8") (pin "M1") (pinfunction "P$2_M1") (pintype "bidirectional"))
    )
    (net (code "129") (name "Net-(A10V-P$2)") (class "Default")
      (node (ref "A10") (pin "M2") (pinfunction "P$2_M2") (pintype "bidirectional"))
      (node (ref "A8") (pin "M2") (pinfunction "P$2_M2") (pintype "bidirectional"))
    )
    (net (code "130") (name "Net-(A10W-P$2)") (class "Default")
      (node (ref "A10") (pin "N1") (pinfunction "P$2_N1") (pintype "bidirectional"))
      (node (ref "A8") (pin "N1") (pinfunction "P$2_N1") (pintype "bidirectional"))
    )
    (net (code "131") (name "Net-(A10X-P$2)") (class "Default")
      (node (ref "A10") (pin "N2") (pinfunction "P$2_N2") (pintype "bidirectional"))
      (node (ref "A8") (pin "N2") (pinfunction "P$2_N2") (pintype "bidirectional"))
    )
    (net (code "132") (name "Net-(A10Y-P$2)") (class "Default")
      (node (ref "A10") (pin "P1") (pinfunction "P$2_P1") (pintype "bidirectional"))
      (node (ref "A8") (pin "P1") (pinfunction "P$2_P1") (pintype "bidirectional"))
    )
    (net (code "133") (name "Net-(A10Z-P$2)") (class "Default")
      (node (ref "A10") (pin "P2") (pinfunction "P$2_P2") (pintype "bidirectional"))
      (node (ref "A8") (pin "P2") (pinfunction "P$2_P2") (pintype "bidirectional"))
    )
    (net (code "134") (name "Net-(A11A-P$2)") (class "Default")
      (node (ref "A11") (pin "A1") (pinfunction "P$2_A1") (pintype "bidirectional"))
      (node (ref "A12") (pin "A1") (pinfunction "P$2_A1") (pintype "bidirectional"))
    )
    (net (code "135") (name "Net-(A11AA-P$2)") (class "Default")
      (node (ref "A11") (pin "R1") (pinfunction "P$2_R1") (pintype "bidirectional"))
      (node (ref "A12") (pin "R1") (pinfunction "P$2_R1") (pintype "bidirectional"))
    )
    (net (code "136") (name "Net-(A11AB-P$2)") (class "Default")
      (node (ref "A11") (pin "R2") (pinfunction "P$2_R2") (pintype "bidirectional"))
      (node (ref "A12") (pin "R2") (pinfunction "P$2_R2") (pintype "bidirectional"))
    )
    (net (code "137") (name "Net-(A11AC-P$2)") (class "Default")
      (node (ref "A11") (pin "S1") (pinfunction "P$2_S1") (pintype "bidirectional"))
      (node (ref "A12") (pin "S1") (pinfunction "P$2_S1") (pintype "bidirectional"))
    )
    (net (code "138") (name "Net-(A11AD-P$2)") (class "Default")
      (node (ref "A11") (pin "S2") (pinfunction "P$2_S2") (pintype "bidirectional"))
      (node (ref "A12") (pin "S2") (pinfunction "P$2_S2") (pintype "bidirectional"))
    )
    (net (code "139") (name "Net-(A11AE-P$2)") (class "Default")
      (node (ref "A11") (pin "T1") (pinfunction "P$2_T1") (pintype "bidirectional"))
      (node (ref "A12") (pin "T1") (pinfunction "P$2_T1") (pintype "bidirectional"))
    )
    (net (code "140") (name "Net-(A11AF-P$2)") (class "Default")
      (node (ref "A11") (pin "T2") (pinfunction "P$2_T2") (pintype "bidirectional"))
      (node (ref "A12") (pin "T2") (pinfunction "P$2_T2") (pintype "bidirectional"))
    )
    (net (code "141") (name "Net-(A11AG-P$2)") (class "Default")
      (node (ref "A11") (pin "U1") (pinfunction "P$2_U1") (pintype "bidirectional"))
      (node (ref "A12") (pin "U1") (pinfunction "P$2_U1") (pintype "bidirectional"))
    )
    (net (code "142") (name "Net-(A11AH-P$2)") (class "Default")
      (node (ref "A11") (pin "U2") (pinfunction "P$2_U2") (pintype "bidirectional"))
      (node (ref "A12") (pin "U2") (pinfunction "P$2_U2") (pintype "bidirectional"))
    )
    (net (code "143") (name "Net-(A11AI-P$2)") (class "Default")
      (node (ref "A11") (pin "V1") (pinfunction "P$2_V1") (pintype "bidirectional"))
      (node (ref "A12") (pin "V1") (pinfunction "P$2_V1") (pintype "bidirectional"))
    )
    (net (code "144") (name "Net-(A11AJ-P$2)") (class "Default")
      (node (ref "A11") (pin "V2") (pinfunction "P$2_V2") (pintype "bidirectional"))
      (node (ref "A12") (pin "V2") (pinfunction "P$2_V2") (pintype "bidirectional"))
    )
    (net (code "145") (name "Net-(A11B-P$2)") (class "Default")
      (node (ref "A11") (pin "A2") (pinfunction "P$2_A2") (pintype "bidirectional"))
      (node (ref "A12") (pin "A2") (pinfunction "P$2_A2") (pintype "bidirectional"))
    )
    (net (code "146") (name "Net-(A11C-P$2)") (class "Default")
      (node (ref "A11") (pin "B1") (pinfunction "P$2_B1") (pintype "bidirectional"))
      (node (ref "A12") (pin "B1") (pinfunction "P$2_B1") (pintype "bidirectional"))
    )
    (net (code "147") (name "Net-(A11D-P$2)") (class "Default")
      (node (ref "A11") (pin "B2") (pinfunction "P$2_B2") (pintype "bidirectional"))
      (node (ref "A12") (pin "B2") (pinfunction "P$2_B2") (pintype "bidirectional"))
    )
    (net (code "148") (name "Net-(A11E-P$2)") (class "Default")
      (node (ref "A11") (pin "C1") (pinfunction "P$2_C1") (pintype "bidirectional"))
      (node (ref "A12") (pin "C1") (pinfunction "P$2_C1") (pintype "bidirectional"))
    )
    (net (code "149") (name "Net-(A11F-P$2)") (class "Default")
      (node (ref "A11") (pin "C2") (pinfunction "P$2_C2") (pintype "bidirectional"))
      (node (ref "A12") (pin "C2") (pinfunction "P$2_C2") (pintype "bidirectional"))
    )
    (net (code "150") (name "Net-(A11G-P$2)") (class "Default")
      (node (ref "A11") (pin "D1") (pinfunction "P$2_D1") (pintype "bidirectional"))
      (node (ref "A12") (pin "D1") (pinfunction "P$2_D1") (pintype "bidirectional"))
    )
    (net (code "151") (name "Net-(A11H-P$2)") (class "Default")
      (node (ref "A11") (pin "D2") (pinfunction "P$2_D2") (pintype "bidirectional"))
      (node (ref "A12") (pin "D2") (pinfunction "P$2_D2") (pintype "bidirectional"))
    )
    (net (code "152") (name "Net-(A11I-P$2)") (class "Default")
      (node (ref "A11") (pin "E1") (pinfunction "P$2_E1") (pintype "bidirectional"))
      (node (ref "A12") (pin "E1") (pinfunction "P$2_E1") (pintype "bidirectional"))
    )
    (net (code "153") (name "Net-(A11J-P$2)") (class "Default")
      (node (ref "A11") (pin "E2") (pinfunction "P$2_E2") (pintype "bidirectional"))
      (node (ref "A12") (pin "E2") (pinfunction "P$2_E2") (pintype "bidirectional"))
    )
    (net (code "154") (name "Net-(A11K-P$2)") (class "Default")
      (node (ref "A11") (pin "F1") (pinfunction "P$2_F1") (pintype "bidirectional"))
      (node (ref "A12") (pin "F1") (pinfunction "P$2_F1") (pintype "bidirectional"))
    )
    (net (code "155") (name "Net-(A11L-P$2)") (class "Default")
      (node (ref "A11") (pin "F2") (pinfunction "P$2_F2") (pintype "bidirectional"))
      (node (ref "A12") (pin "F2") (pinfunction "P$2_F2") (pintype "bidirectional"))
    )
    (net (code "156") (name "Net-(A11M-P$2)") (class "Default")
      (node (ref "A11") (pin "H1") (pinfunction "P$2_H1") (pintype "bidirectional"))
      (node (ref "A12") (pin "H1") (pinfunction "P$2_H1") (pintype "bidirectional"))
    )
    (net (code "157") (name "Net-(A11N-P$2)") (class "Default")
      (node (ref "A11") (pin "H2") (pinfunction "P$2_H2") (pintype "bidirectional"))
      (node (ref "A12") (pin "H2") (pinfunction "P$2_H2") (pintype "bidirectional"))
    )
    (net (code "158") (name "Net-(A11O-P$2)") (class "Default")
      (node (ref "A11") (pin "J1") (pinfunction "P$2_J1") (pintype "bidirectional"))
      (node (ref "A12") (pin "J1") (pinfunction "P$2_J1") (pintype "bidirectional"))
    )
    (net (code "159") (name "Net-(A11P-P$2)") (class "Default")
      (node (ref "A11") (pin "J2") (pinfunction "P$2_J2") (pintype "bidirectional"))
      (node (ref "A12") (pin "J2") (pinfunction "P$2_J2") (pintype "bidirectional"))
    )
    (net (code "160") (name "Net-(A11Q-P$2)") (class "Default")
      (node (ref "A11") (pin "K1") (pinfunction "P$2_K1") (pintype "bidirectional"))
      (node (ref "A12") (pin "K1") (pinfunction "P$2_K1") (pintype "bidirectional"))
    )
    (net (code "161") (name "Net-(A11R-P$2)") (class "Default")
      (node (ref "A11") (pin "K2") (pinfunction "P$2_K2") (pintype "bidirectional"))
      (node (ref "A12") (pin "K2") (pinfunction "P$2_K2") (pintype "bidirectional"))
    )
    (net (code "162") (name "Net-(A11S-P$2)") (class "Default")
      (node (ref "A11") (pin "L1") (pinfunction "P$2_L1") (pintype "bidirectional"))
      (node (ref "A12") (pin "L1") (pinfunction "P$2_L1") (pintype "bidirectional"))
    )
    (net (code "163") (name "Net-(A11T-P$2)") (class "Default")
      (node (ref "A11") (pin "L2") (pinfunction "P$2_L2") (pintype "bidirectional"))
      (node (ref "A12") (pin "L2") (pinfunction "P$2_L2") (pintype "bidirectional"))
    )
    (net (code "164") (name "Net-(A11U-P$2)") (class "Default")
      (node (ref "A11") (pin "M1") (pinfunction "P$2_M1") (pintype "bidirectional"))
      (node (ref "A12") (pin "M1") (pinfunction "P$2_M1") (pintype "bidirectional"))
    )
    (net (code "165") (name "Net-(A11V-P$2)") (class "Default")
      (node (ref "A11") (pin "M2") (pinfunction "P$2_M2") (pintype "bidirectional"))
      (node (ref "A12") (pin "M2") (pinfunction "P$2_M2") (pintype "bidirectional"))
    )
    (net (code "166") (name "Net-(A11W-P$2)") (class "Default")
      (node (ref "A11") (pin "N1") (pinfunction "P$2_N1") (pintype "bidirectional"))
      (node (ref "A12") (pin "N1") (pinfunction "P$2_N1") (pintype "bidirectional"))
    )
    (net (code "167") (name "Net-(A11X-P$2)") (class "Default")
      (node (ref "A11") (pin "N2") (pinfunction "P$2_N2") (pintype "bidirectional"))
      (node (ref "A12") (pin "N2") (pinfunction "P$2_N2") (pintype "bidirectional"))
    )
    (net (code "168") (name "Net-(A11Y-P$2)") (class "Default")
      (node (ref "A11") (pin "P1") (pinfunction "P$2_P1") (pintype "bidirectional"))
      (node (ref "A12") (pin "P1") (pinfunction "P$2_P1") (pintype "bidirectional"))
    )
    (net (code "169") (name "Net-(A11Z-P$2)") (class "Default")
      (node (ref "A11") (pin "P2") (pinfunction "P$2_P2") (pintype "bidirectional"))
      (node (ref "A12") (pin "P2") (pinfunction "P$2_P2") (pintype "bidirectional"))
    )
    (net (code "170") (name "Net-(IC1A-I)") (class "Default")
      (node (ref "IC1") (pin "2") (pinfunction "I_2") (pintype "input"))
      (node (ref "OUT1-2") (pin "2") (pinfunction "2_2") (pintype "passive"))
    )
    (net (code "171") (name "Net-(IC1A-OE)") (class "Default")
      (node (ref "IC1") (pin "1") (pinfunction "OE_1") (pintype "input"))
      (node (ref "OUT1-2") (pin "1") (pinfunction "1_1") (pintype "passive"))
    )
    (net (code "172") (name "Net-(IC1B-I)") (class "Default")
      (node (ref "IC1") (pin "5") (pinfunction "I_5") (pintype "input"))
      (node (ref "OUT1-2") (pin "4") (pinfunction "4_4") (pintype "passive"))
    )
    (net (code "173") (name "Net-(IC1B-OE)") (class "Default")
      (node (ref "IC1") (pin "4") (pinfunction "OE_4") (pintype "input"))
      (node (ref "OUT1-2") (pin "3") (pinfunction "3_3") (pintype "passive"))
    )
    (net (code "174") (name "Net-(IC1C-I)") (class "Default")
      (node (ref "IC1") (pin "9") (pinfunction "I_9") (pintype "input"))
      (node (ref "OUT1-2") (pin "6") (pinfunction "6_6") (pintype "passive"))
    )
    (net (code "175") (name "Net-(IC1C-OE)") (class "Default")
      (node (ref "IC1") (pin "10") (pinfunction "OE_10") (pintype "input"))
      (node (ref "OUT1-2") (pin "5") (pinfunction "5_5") (pintype "passive"))
    )
    (net (code "176") (name "Net-(IC1D-I)") (class "Default")
      (node (ref "IC1") (pin "12") (pinfunction "I_12") (pintype "input"))
      (node (ref "OUT1-2") (pin "8") (pinfunction "8_8") (pintype "passive"))
    )
    (net (code "177") (name "Net-(IC1D-OE)") (class "Default")
      (node (ref "IC1") (pin "13") (pinfunction "OE_13") (pintype "input"))
      (node (ref "OUT1-2") (pin "7") (pinfunction "7_7") (pintype "passive"))
    )
    (net (code "178") (name "Net-(IC2A-I)") (class "Default")
      (node (ref "IC2") (pin "2") (pinfunction "I_2") (pintype "input"))
      (node (ref "OUT1-2") (pin "10") (pinfunction "10_10") (pintype "passive"))
    )
    (net (code "179") (name "Net-(IC2A-OE)") (class "Default")
      (node (ref "IC2") (pin "1") (pinfunction "OE_1") (pintype "input"))
      (node (ref "OUT1-2") (pin "9") (pinfunction "9_9") (pintype "passive"))
    )
    (net (code "180") (name "Net-(IC2B-I)") (class "Default")
      (node (ref "IC2") (pin "5") (pinfunction "I_5") (pintype "input"))
      (node (ref "OUT1-2") (pin "12") (pinfunction "12_12") (pintype "passive"))
    )
    (net (code "181") (name "Net-(IC2B-OE)") (class "Default")
      (node (ref "IC2") (pin "4") (pinfunction "OE_4") (pintype "input"))
      (node (ref "OUT1-2") (pin "11") (pinfunction "11_11") (pintype "passive"))
    )
    (net (code "182") (name "Net-(IC2C-I)") (class "Default")
      (node (ref "IC2") (pin "9") (pinfunction "I_9") (pintype "input"))
      (node (ref "OUT1-2") (pin "14") (pinfunction "14_14") (pintype "passive"))
    )
    (net (code "183") (name "Net-(IC2C-OE)") (class "Default")
      (node (ref "IC2") (pin "10") (pinfunction "OE_10") (pintype "input"))
      (node (ref "OUT1-2") (pin "13") (pinfunction "13_13") (pintype "passive"))
    )
    (net (code "184") (name "Net-(IC2D-I)") (class "Default")
      (node (ref "IC2") (pin "12") (pinfunction "I_12") (pintype "input"))
      (node (ref "OUT1-2") (pin "16") (pinfunction "16_16") (pintype "passive"))
    )
    (net (code "185") (name "Net-(IC2D-OE)") (class "Default")
      (node (ref "IC2") (pin "13") (pinfunction "OE_13") (pintype "input"))
      (node (ref "OUT1-2") (pin "15") (pinfunction "15_15") (pintype "passive"))
    )
    (net (code "186") (name "Net-(IC3A-I)") (class "Default")
      (node (ref "IC3") (pin "2") (pinfunction "I_2") (pintype "input"))
      (node (ref "OUT3-4") (pin "2") (pinfunction "2_2") (pintype "passive"))
    )
    (net (code "187") (name "Net-(IC3A-OE)") (class "Default")
      (node (ref "IC3") (pin "1") (pinfunction "OE_1") (pintype "input"))
      (node (ref "OUT3-4") (pin "1") (pinfunction "1_1") (pintype "passive"))
    )
    (net (code "188") (name "Net-(IC3B-I)") (class "Default")
      (node (ref "IC3") (pin "5") (pinfunction "I_5") (pintype "input"))
      (node (ref "OUT3-4") (pin "4") (pinfunction "4_4") (pintype "passive"))
    )
    (net (code "189") (name "Net-(IC3B-OE)") (class "Default")
      (node (ref "IC3") (pin "4") (pinfunction "OE_4") (pintype "input"))
      (node (ref "OUT3-4") (pin "3") (pinfunction "3_3") (pintype "passive"))
    )
    (net (code "190") (name "Net-(IC3C-I)") (class "Default")
      (node (ref "IC3") (pin "9") (pinfunction "I_9") (pintype "input"))
      (node (ref "OUT3-4") (pin "6") (pinfunction "6_6") (pintype "passive"))
    )
    (net (code "191") (name "Net-(IC3C-OE)") (class "Default")
      (node (ref "IC3") (pin "10") (pinfunction "OE_10") (pintype "input"))
      (node (ref "OUT3-4") (pin "5") (pinfunction "5_5") (pintype "passive"))
    )
    (net (code "192") (name "Net-(IC3D-I)") (class "Default")
      (node (ref "IC3") (pin "12") (pinfunction "I_12") (pintype "input"))
      (node (ref "OUT3-4") (pin "8") (pinfunction "8_8") (pintype "passive"))
    )
    (net (code "193") (name "Net-(IC3D-OE)") (class "Default")
      (node (ref "IC3") (pin "13") (pinfunction "OE_13") (pintype "input"))
      (node (ref "OUT3-4") (pin "7") (pinfunction "7_7") (pintype "passive"))
    )
    (net (code "194") (name "Net-(IC4A-I)") (class "Default")
      (node (ref "IC4") (pin "2") (pinfunction "I_2") (pintype "input"))
      (node (ref "OUT3-4") (pin "10") (pinfunction "10_10") (pintype "passive"))
    )
    (net (code "195") (name "Net-(IC4A-OE)") (class "Default")
      (node (ref "IC4") (pin "1") (pinfunction "OE_1") (pintype "input"))
      (node (ref "OUT3-4") (pin "9") (pinfunction "9_9") (pintype "passive"))
    )
    (net (code "196") (name "Net-(IC4B-I)") (class "Default")
      (node (ref "IC4") (pin "5") (pinfunction "I_5") (pintype "input"))
      (node (ref "OUT3-4") (pin "12") (pinfunction "12_12") (pintype "passive"))
    )
    (net (code "197") (name "Net-(IC4B-OE)") (class "Default")
      (node (ref "IC4") (pin "4") (pinfunction "OE_4") (pintype "input"))
      (node (ref "OUT3-4") (pin "11") (pinfunction "11_11") (pintype "passive"))
    )
    (net (code "198") (name "Net-(IC4C-I)") (class "Default")
      (node (ref "IC4") (pin "9") (pinfunction "I_9") (pintype "input"))
      (node (ref "OUT3-4") (pin "14") (pinfunction "14_14") (pintype "passive"))
    )
    (net (code "199") (name "Net-(IC4C-OE)") (class "Default")
      (node (ref "IC4") (pin "10") (pinfunction "OE_10") (pintype "input"))
      (node (ref "OUT3-4") (pin "13") (pinfunction "13_13") (pintype "passive"))
    )
    (net (code "200") (name "Net-(IC4D-I)") (class "Default")
      (node (ref "IC4") (pin "12") (pinfunction "I_12") (pintype "input"))
      (node (ref "OUT3-4") (pin "16") (pinfunction "16_16") (pintype "passive"))
    )
    (net (code "201") (name "Net-(IC4D-OE)") (class "Default")
      (node (ref "IC4") (pin "13") (pinfunction "OE_13") (pintype "input"))
      (node (ref "OUT3-4") (pin "15") (pinfunction "15_15") (pintype "passive"))
    )
    (net (code "202") (name "Net-(IC5A-I)") (class "Default")
      (node (ref "IC5") (pin "2") (pinfunction "I_2") (pintype "input"))
      (node (ref "OUT5-6") (pin "2") (pinfunction "2_2") (pintype "passive"))
    )
    (net (code "203") (name "Net-(IC5A-OE)") (class "Default")
      (node (ref "IC5") (pin "1") (pinfunction "OE_1") (pintype "input"))
      (node (ref "OUT5-6") (pin "1") (pinfunction "1_1") (pintype "passive"))
    )
    (net (code "204") (name "Net-(IC5B-I)") (class "Default")
      (node (ref "IC5") (pin "5") (pinfunction "I_5") (pintype "input"))
      (node (ref "OUT5-6") (pin "4") (pinfunction "4_4") (pintype "passive"))
    )
    (net (code "205") (name "Net-(IC5B-OE)") (class "Default")
      (node (ref "IC5") (pin "4") (pinfunction "OE_4") (pintype "input"))
      (node (ref "OUT5-6") (pin "3") (pinfunction "3_3") (pintype "passive"))
    )
    (net (code "206") (name "Net-(IC5C-I)") (class "Default")
      (node (ref "IC5") (pin "9") (pinfunction "I_9") (pintype "input"))
      (node (ref "OUT5-6") (pin "6") (pinfunction "6_6") (pintype "passive"))
    )
    (net (code "207") (name "Net-(IC5C-OE)") (class "Default")
      (node (ref "IC5") (pin "10") (pinfunction "OE_10") (pintype "input"))
      (node (ref "OUT5-6") (pin "5") (pinfunction "5_5") (pintype "passive"))
    )
    (net (code "208") (name "Net-(IC5D-I)") (class "Default")
      (node (ref "IC5") (pin "12") (pinfunction "I_12") (pintype "input"))
      (node (ref "OUT5-6") (pin "8") (pinfunction "8_8") (pintype "passive"))
    )
    (net (code "209") (name "Net-(IC5D-OE)") (class "Default")
      (node (ref "IC5") (pin "13") (pinfunction "OE_13") (pintype "input"))
      (node (ref "OUT5-6") (pin "7") (pinfunction "7_7") (pintype "passive"))
    )
    (net (code "210") (name "Net-(IC6A-I)") (class "Default")
      (node (ref "IC6") (pin "2") (pinfunction "I_2") (pintype "input"))
      (node (ref "OUT5-6") (pin "10") (pinfunction "10_10") (pintype "passive"))
    )
    (net (code "211") (name "Net-(IC6A-OE)") (class "Default")
      (node (ref "IC6") (pin "1") (pinfunction "OE_1") (pintype "input"))
      (node (ref "OUT5-6") (pin "9") (pinfunction "9_9") (pintype "passive"))
    )
    (net (code "212") (name "Net-(IC6B-I)") (class "Default")
      (node (ref "IC6") (pin "5") (pinfunction "I_5") (pintype "input"))
      (node (ref "OUT5-6") (pin "12") (pinfunction "12_12") (pintype "passive"))
    )
    (net (code "213") (name "Net-(IC6B-OE)") (class "Default")
      (node (ref "IC6") (pin "4") (pinfunction "OE_4") (pintype "input"))
      (node (ref "OUT5-6") (pin "11") (pinfunction "11_11") (pintype "passive"))
    )
    (net (code "214") (name "Net-(IC6C-I)") (class "Default")
      (node (ref "IC6") (pin "9") (pinfunction "I_9") (pintype "input"))
      (node (ref "OUT5-6") (pin "14") (pinfunction "14_14") (pintype "passive"))
    )
    (net (code "215") (name "Net-(IC6C-OE)") (class "Default")
      (node (ref "IC6") (pin "10") (pinfunction "OE_10") (pintype "input"))
      (node (ref "OUT5-6") (pin "13") (pinfunction "13_13") (pintype "passive"))
    )
    (net (code "216") (name "Net-(IC6D-I)") (class "Default")
      (node (ref "IC6") (pin "12") (pinfunction "I_12") (pintype "input"))
      (node (ref "OUT5-6") (pin "16") (pinfunction "16_16") (pintype "passive"))
    )
    (net (code "217") (name "Net-(IC6D-OE)") (class "Default")
      (node (ref "IC6") (pin "13") (pinfunction "OE_13") (pintype "input"))
      (node (ref "OUT5-6") (pin "15") (pinfunction "15_15") (pintype "passive"))
    )
    (net (code "218") (name "Net-(IC7A-I)") (class "Default")
      (node (ref "IC7") (pin "2") (pinfunction "I_2") (pintype "input"))
      (node (ref "OUT7-8") (pin "2") (pinfunction "2_2") (pintype "passive"))
    )
    (net (code "219") (name "Net-(IC7A-OE)") (class "Default")
      (node (ref "IC7") (pin "1") (pinfunction "OE_1") (pintype "input"))
      (node (ref "OUT7-8") (pin "1") (pinfunction "1_1") (pintype "passive"))
    )
    (net (code "220") (name "Net-(IC7B-I)") (class "Default")
      (node (ref "IC7") (pin "5") (pinfunction "I_5") (pintype "input"))
      (node (ref "OUT7-8") (pin "4") (pinfunction "4_4") (pintype "passive"))
    )
    (net (code "221") (name "Net-(IC7B-OE)") (class "Default")
      (node (ref "IC7") (pin "4") (pinfunction "OE_4") (pintype "input"))
      (node (ref "OUT7-8") (pin "3") (pinfunction "3_3") (pintype "passive"))
    )
    (net (code "222") (name "Net-(IC7C-I)") (class "Default")
      (node (ref "IC7") (pin "9") (pinfunction "I_9") (pintype "input"))
      (node (ref "OUT7-8") (pin "6") (pinfunction "6_6") (pintype "passive"))
    )
    (net (code "223") (name "Net-(IC7C-OE)") (class "Default")
      (node (ref "IC7") (pin "10") (pinfunction "OE_10") (pintype "input"))
      (node (ref "OUT7-8") (pin "5") (pinfunction "5_5") (pintype "passive"))
    )
    (net (code "224") (name "Net-(IC7D-I)") (class "Default")
      (node (ref "IC7") (pin "12") (pinfunction "I_12") (pintype "input"))
      (node (ref "OUT7-8") (pin "8") (pinfunction "8_8") (pintype "passive"))
    )
    (net (code "225") (name "Net-(IC7D-OE)") (class "Default")
      (node (ref "IC7") (pin "13") (pinfunction "OE_13") (pintype "input"))
      (node (ref "OUT7-8") (pin "7") (pinfunction "7_7") (pintype "passive"))
    )
    (net (code "226") (name "Net-(IC8A-I)") (class "Default")
      (node (ref "IC8") (pin "2") (pinfunction "I_2") (pintype "input"))
      (node (ref "OUT7-8") (pin "10") (pinfunction "10_10") (pintype "passive"))
    )
    (net (code "227") (name "Net-(IC8A-OE)") (class "Default")
      (node (ref "IC8") (pin "1") (pinfunction "OE_1") (pintype "input"))
      (node (ref "OUT7-8") (pin "9") (pinfunction "9_9") (pintype "passive"))
    )
    (net (code "228") (name "Net-(IC8B-I)") (class "Default")
      (node (ref "IC8") (pin "5") (pinfunction "I_5") (pintype "input"))
      (node (ref "OUT7-8") (pin "12") (pinfunction "12_12") (pintype "passive"))
    )
    (net (code "229") (name "Net-(IC8B-OE)") (class "Default")
      (node (ref "IC8") (pin "4") (pinfunction "OE_4") (pintype "input"))
      (node (ref "OUT7-8") (pin "11") (pinfunction "11_11") (pintype "passive"))
    )
    (net (code "230") (name "Net-(IC8C-I)") (class "Default")
      (node (ref "IC8") (pin "9") (pinfunction "I_9") (pintype "input"))
      (node (ref "OUT7-8") (pin "14") (pinfunction "14_14") (pintype "passive"))
    )
    (net (code "231") (name "Net-(IC8C-OE)") (class "Default")
      (node (ref "IC8") (pin "10") (pinfunction "OE_10") (pintype "input"))
      (node (ref "OUT7-8") (pin "13") (pinfunction "13_13") (pintype "passive"))
    )
    (net (code "232") (name "Net-(IC8D-I)") (class "Default")
      (node (ref "IC8") (pin "12") (pinfunction "I_12") (pintype "input"))
      (node (ref "OUT7-8") (pin "16") (pinfunction "16_16") (pintype "passive"))
    )
    (net (code "233") (name "Net-(IC8D-OE)") (class "Default")
      (node (ref "IC8") (pin "13") (pinfunction "OE_13") (pintype "input"))
      (node (ref "OUT7-8") (pin "15") (pinfunction "15_15") (pintype "passive"))
    )
    (net (code "234") (name "Net-(IC9A-O)") (class "Default")
      (node (ref "IC9") (pin "3") (pinfunction "O_3") (pintype "output"))
      (node (ref "IC9") (pin "4") (pinfunction "I0_4") (pintype "input"))
    )
    (net (code "235") (name "Net-(IC9B-O)") (class "Default")
      (node (ref "IC9") (pin "12") (pinfunction "I0_12") (pintype "input"))
      (node (ref "IC9") (pin "6") (pinfunction "O_6") (pintype "output"))
    )
    (net (code "236") (name "Net-(IC9C-I1)") (class "Default")
      (node (ref "C1") (pin "1") (pinfunction "1_1") (pintype "passive"))
      (node (ref "IC9") (pin "10") (pinfunction "I1_10") (pintype "input"))
      (node (ref "R1") (pin "1") (pinfunction "1_1") (pintype "passive"))
    )
    (net (code "237") (name "OA1") (class "Default")
      (node (ref "A1-K1") (pin "18") (pinfunction "18_18") (pintype "passive"))
      (node (ref "IC1") (pin "3") (pinfunction "O_3") (pintype "tri_state"))
      (node (ref "JP1") (pin "1") (pinfunction "1_1") (pintype "passive"))
    )
    (net (code "238") (name "OB1") (class "Default")
      (node (ref "A1-K1") (pin "17") (pinfunction "17_17") (pintype "passive"))
      (node (ref "IC1") (pin "6") (pinfunction "O_6") (pintype "tri_state"))
      (node (ref "JP1") (pin "2") (pinfunction "2_2") (pintype "passive"))
    )
    (net (code "239") (name "OB2") (class "Default")
      (node (ref "A2-K2") (pin "17") (pinfunction "17_17") (pintype "passive"))
      (node (ref "JP2") (pin "2") (pinfunction "2_2") (pintype "passive"))
    )
    (net (code "240") (name "OC") (class "Default")
      (node (ref "IC9") (pin "13") (pinfunction "I1_13") (pintype "input"))
      (node (ref "IC9") (pin "8") (pinfunction "O_8") (pintype "output"))
      (node (ref "IN5-6") (pin "1") (pinfunction "1_1") (pintype "passive"))
      (node (ref "OC") (pin "1") (pinfunction "1_1") (pintype "passive"))
    )
    (net (code "241") (name "OC1") (class "Default")
      (node (ref "A1-K1") (pin "16") (pinfunction "16_16") (pintype "passive"))
      (node (ref "IC1") (pin "8") (pinfunction "O_8") (pintype "tri_state"))
      (node (ref "JP1") (pin "3") (pinfunction "3_3") (pintype "passive"))
    )
    (net (code "242") (name "OD1") (class "Default")
      (node (ref "A1-K1") (pin "15") (pinfunction "15_15") (pintype "passive"))
      (node (ref "IC1") (pin "11") (pinfunction "O_11") (pintype "tri_state"))
      (node (ref "JP1") (pin "4") (pinfunction "4_4") (pintype "passive"))
    )
    (net (code "243") (name "OD2") (class "Default")
      (node (ref "A2-K2") (pin "15") (pinfunction "15_15") (pintype "passive"))
      (node (ref "IC5") (pin "6") (pinfunction "O_6") (pintype "tri_state"))
      (node (ref "JP2") (pin "4") (pinfunction "4_4") (pintype "passive"))
    )
    (net (code "244") (name "OE1") (class "Default")
      (node (ref "A1-K1") (pin "14") (pinfunction "14_14") (pintype "passive"))
      (node (ref "IC2") (pin "3") (pinfunction "O_3") (pintype "tri_state"))
      (node (ref "JP1") (pin "5") (pinfunction "5_5") (pintype "passive"))
    )
    (net (code "245") (name "OE2") (class "Default")
      (node (ref "A2-K2") (pin "14") (pinfunction "14_14") (pintype "passive"))
      (node (ref "IC5") (pin "8") (pinfunction "O_8") (pintype "tri_state"))
      (node (ref "JP2") (pin "5") (pinfunction "5_5") (pintype "passive"))
    )
    (net (code "246") (name "OF1") (class "Default")
      (node (ref "A1-K1") (pin "13") (pinfunction "13_13") (pintype "passive"))
      (node (ref "IC2") (pin "6") (pinfunction "O_6") (pintype "tri_state"))
      (node (ref "JP1") (pin "6") (pinfunction "6_6") (pintype "passive"))
    )
    (net (code "247") (name "OF2") (class "Default")
      (node (ref "A2-K2") (pin "13") (pinfunction "13_13") (pintype "passive"))
      (node (ref "IC5") (pin "11") (pinfunction "O_11") (pintype "tri_state"))
      (node (ref "JP2") (pin "6") (pinfunction "6_6") (pintype "passive"))
    )
    (net (code "248") (name "OH1") (class "Default")
      (node (ref "A1-K1") (pin "12") (pinfunction "12_12") (pintype "passive"))
      (node (ref "IC2") (pin "8") (pinfunction "O_8") (pintype "tri_state"))
      (node (ref "JP1") (pin "7") (pinfunction "7_7") (pintype "passive"))
    )
    (net (code "249") (name "OH2") (class "Default")
      (node (ref "A2-K2") (pin "12") (pinfunction "12_12") (pintype "passive"))
      (node (ref "IC6") (pin "3") (pinfunction "O_3") (pintype "tri_state"))
      (node (ref "JP2") (pin "7") (pinfunction "7_7") (pintype "passive"))
    )
    (net (code "250") (name "OJ1") (class "Default")
      (node (ref "A1-K1") (pin "11") (pinfunction "11_11") (pintype "passive"))
      (node (ref "IC2") (pin "11") (pinfunction "O_11") (pintype "tri_state"))
      (node (ref "JP1") (pin "8") (pinfunction "8_8") (pintype "passive"))
    )
    (net (code "251") (name "OJ2") (class "Default")
      (node (ref "A2-K2") (pin "11") (pinfunction "11_11") (pintype "passive"))
      (node (ref "IC6") (pin "6") (pinfunction "O_6") (pintype "tri_state"))
      (node (ref "JP2") (pin "8") (pinfunction "8_8") (pintype "passive"))
    )
    (net (code "252") (name "OK1") (class "Default")
      (node (ref "A1-K1") (pin "10") (pinfunction "10_10") (pintype "passive"))
      (node (ref "IC3") (pin "3") (pinfunction "O_3") (pintype "tri_state"))
      (node (ref "JP1") (pin "9") (pinfunction "9_9") (pintype "passive"))
    )
    (net (code "253") (name "OK2") (class "Default")
      (node (ref "A2-K2") (pin "10") (pinfunction "10_10") (pintype "passive"))
      (node (ref "IC6") (pin "8") (pinfunction "O_8") (pintype "tri_state"))
      (node (ref "JP2") (pin "9") (pinfunction "9_9") (pintype "passive"))
    )
    (net (code "254") (name "OL1") (class "Default")
      (node (ref "IC3") (pin "6") (pinfunction "O_6") (pintype "tri_state"))
      (node (ref "JP1") (pin "10") (pinfunction "10_10") (pintype "passive"))
      (node (ref "L1-V1") (pin "18") (pinfunction "18_18") (pintype "passive"))
    )
    (net (code "255") (name "OL2") (class "Default")
      (node (ref "IC6") (pin "11") (pinfunction "O_11") (pintype "tri_state"))
      (node (ref "JP2") (pin "10") (pinfunction "10_10") (pintype "passive"))
      (node (ref "L2-V2") (pin "18") (pinfunction "18_18") (pintype "passive"))
    )
    (net (code "256") (name "OM1") (class "Default")
      (node (ref "IC3") (pin "8") (pinfunction "O_8") (pintype "tri_state"))
      (node (ref "JP1") (pin "11") (pinfunction "11_11") (pintype "passive"))
      (node (ref "L1-V1") (pin "17") (pinfunction "17_17") (pintype "passive"))
    )
    (net (code "257") (name "OM2") (class "Default")
      (node (ref "IC7") (pin "3") (pinfunction "O_3") (pintype "tri_state"))
      (node (ref "JP2") (pin "11") (pinfunction "11_11") (pintype "passive"))
      (node (ref "L2-V2") (pin "17") (pinfunction "17_17") (pintype "passive"))
    )
    (net (code "258") (name "ON1") (class "Default")
      (node (ref "IC3") (pin "11") (pinfunction "O_11") (pintype "tri_state"))
      (node (ref "JP1") (pin "12") (pinfunction "12_12") (pintype "passive"))
      (node (ref "L1-V1") (pin "16") (pinfunction "16_16") (pintype "passive"))
    )
    (net (code "259") (name "ON2") (class "Default")
      (node (ref "IC7") (pin "6") (pinfunction "O_6") (pintype "tri_state"))
      (node (ref "JP2") (pin "12") (pinfunction "12_12") (pintype "passive"))
      (node (ref "L2-V2") (pin "16") (pinfunction "16_16") (pintype "passive"))
    )
    (net (code "260") (name "OP1") (class "Default")
      (node (ref "IC4") (pin "3") (pinfunction "O_3") (pintype "tri_state"))
      (node (ref "JP1") (pin "13") (pinfunction "13_13") (pintype "passive"))
      (node (ref "L1-V1") (pin "15") (pinfunction "15_15") (pintype "passive"))
    )
    (net (code "261") (name "OP2") (class "Default")
      (node (ref "IC7") (pin "8") (pinfunction "O_8") (pintype "tri_state"))
      (node (ref "JP2") (pin "13") (pinfunction "13_13") (pintype "passive"))
      (node (ref "L2-V2") (pin "15") (pinfunction "15_15") (pintype "passive"))
    )
    (net (code "262") (name "OR1") (class "Default")
      (node (ref "IC4") (pin "6") (pinfunction "O_6") (pintype "tri_state"))
      (node (ref "JP1") (pin "14") (pinfunction "14_14") (pintype "passive"))
      (node (ref "L1-V1") (pin "14") (pinfunction "14_14") (pintype "passive"))
    )
    (net (code "263") (name "OR2") (class "Default")
      (node (ref "IC7") (pin "11") (pinfunction "O_11") (pintype "tri_state"))
      (node (ref "JP2") (pin "14") (pinfunction "14_14") (pintype "passive"))
      (node (ref "L2-V2") (pin "14") (pinfunction "14_14") (pintype "passive"))
    )
    (net (code "264") (name "OS1") (class "Default")
      (node (ref "IC4") (pin "8") (pinfunction "O_8") (pintype "tri_state"))
      (node (ref "JP1") (pin "15") (pinfunction "15_15") (pintype "passive"))
      (node (ref "L1-V1") (pin "13") (pinfunction "13_13") (pintype "passive"))
    )
    (net (code "265") (name "OS2") (class "Default")
      (node (ref "IC8") (pin "3") (pinfunction "O_3") (pintype "tri_state"))
      (node (ref "JP2") (pin "15") (pinfunction "15_15") (pintype "passive"))
      (node (ref "L2-V2") (pin "13") (pinfunction "13_13") (pintype "passive"))
    )
    (net (code "266") (name "OT2") (class "Default")
      (node (ref "IC8") (pin "6") (pinfunction "O_6") (pintype "tri_state"))
      (node (ref "JP2") (pin "16") (pinfunction "16_16") (pintype "passive"))
      (node (ref "L2-V2") (pin "12") (pinfunction "12_12") (pintype "passive"))
    )
    (net (code "267") (name "OU1") (class "Default")
      (node (ref "IC4") (pin "11") (pinfunction "O_11") (pintype "tri_state"))
      (node (ref "JP1") (pin "17") (pinfunction "17_17") (pintype "passive"))
      (node (ref "L1-V1") (pin "11") (pinfunction "11_11") (pintype "passive"))
    )
    (net (code "268") (name "OU2") (class "Default")
      (node (ref "IC8") (pin "8") (pinfunction "O_8") (pintype "tri_state"))
      (node (ref "JP2") (pin "17") (pinfunction "17_17") (pintype "passive"))
      (node (ref "L2-V2") (pin "11") (pinfunction "11_11") (pintype "passive"))
    )
    (net (code "269") (name "OV1") (class "Default")
      (node (ref "IC5") (pin "3") (pinfunction "O_3") (pintype "tri_state"))
      (node (ref "JP1") (pin "18") (pinfunction "18_18") (pintype "passive"))
      (node (ref "L1-V1") (pin "10") (pinfunction "10_10") (pintype "passive"))
    )
    (net (code "270") (name "OV2") (class "Default")
      (node (ref "IC8") (pin "11") (pinfunction "O_11") (pintype "tri_state"))
      (node (ref "JP2") (pin "18") (pinfunction "18_18") (pintype "passive"))
      (node (ref "L2-V2") (pin "10") (pinfunction "10_10") (pintype "passive"))
    )
    (net (code "271") (name "P1") (class "Default")
      (node (ref "IN1-2") (pin "10") (pinfunction "10_10") (pintype "passive"))
      (node (ref "JP3") (pin "13") (pinfunction "13_13") (pintype "passive"))
      (node (ref "L1-V1") (pin "4") (pinfunction "4_4") (pintype "passive"))
      (node (ref "SIDE1") (pin "30") (pinfunction "30_30") (pintype "passive"))
    )
    (net (code "272") (name "P2") (class "Default")
      (node (ref "IN3-4") (pin "13") (pinfunction "13_13") (pintype "passive"))
      (node (ref "JP4") (pin "13") (pinfunction "13_13") (pintype "passive"))
      (node (ref "L2-V2") (pin "4") (pinfunction "4_4") (pintype "passive"))
      (node (ref "SIDE2") (pin "24") (pinfunction "24_24") (pintype "passive"))
    )
    (net (code "273") (name "PIA-B5") (class "Default")
      (node (ref "CORE-IO") (pin "18") (pinfunction "18_18") (pintype "passive"))
      (node (ref "IC9") (pin "5") (pinfunction "I1_5") (pintype "input"))
    )
    (net (code "274") (name "PIA-B7") (class "Default")
      (node (ref "CORE-IO") (pin "20") (pinfunction "20_20") (pintype "passive"))
      (node (ref "IC9") (pin "1") (pinfunction "I0_1") (pintype "input"))
      (node (ref "IC9") (pin "2") (pinfunction "I1_2") (pintype "input"))
    )
    (net (code "275") (name "R1") (class "Default")
      (node (ref "IN1-2") (pin "12") (pinfunction "12_12") (pintype "passive"))
      (node (ref "JP3") (pin "14") (pinfunction "14_14") (pintype "passive"))
      (node (ref "L1-V1") (pin "5") (pinfunction "5_5") (pintype "passive"))
      (node (ref "SIDE1") (pin "26") (pinfunction "26_26") (pintype "passive"))
    )
    (net (code "276") (name "R2") (class "Default")
      (node (ref "IN3-4") (pin "15") (pinfunction "15_15") (pintype "passive"))
      (node (ref "JP4") (pin "14") (pinfunction "14_14") (pintype "passive"))
      (node (ref "L2-V2") (pin "5") (pinfunction "5_5") (pintype "passive"))
      (node (ref "SIDE2") (pin "26") (pinfunction "26_26") (pintype "passive"))
    )
    (net (code "277") (name "S1") (class "Default")
      (node (ref "IN1-2") (pin "14") (pinfunction "14_14") (pintype "passive"))
      (node (ref "JP3") (pin "15") (pinfunction "15_15") (pintype "passive"))
      (node (ref "L1-V1") (pin "6") (pinfunction "6_6") (pintype "passive"))
      (node (ref "SIDE1") (pin "32") (pinfunction "32_32") (pintype "passive"))
    )
    (net (code "278") (name "S2") (class "Default")
      (node (ref "IN3-4") (pin "10") (pinfunction "10_10") (pintype "passive"))
      (node (ref "JP4") (pin "15") (pinfunction "15_15") (pintype "passive"))
      (node (ref "L2-V2") (pin "6") (pinfunction "6_6") (pintype "passive"))
      (node (ref "SIDE2") (pin "28") (pinfunction "28_28") (pintype "passive"))
    )
    (net (code "279") (name "T1") (class "Default")
      (node (ref "JP3") (pin "16") (pinfunction "16_16") (pintype "passive"))
      (node (ref "L1-V1") (pin "7") (pinfunction "7_7") (pintype "passive"))
      (node (ref "SIDE1") (pin "34") (pinfunction "34_34") (pintype "passive"))
    )
    (net (code "280") (name "T2") (class "Default")
      (node (ref "IN3-4") (pin "12") (pinfunction "12_12") (pintype "passive"))
      (node (ref "JP4") (pin "16") (pinfunction "16_16") (pintype "passive"))
      (node (ref "L2-V2") (pin "7") (pinfunction "7_7") (pintype "passive"))
      (node (ref "SIDE2") (pin "30") (pinfunction "30_30") (pintype "passive"))
    )
    (net (code "281") (name "U1") (class "Default")
      (node (ref "IN1-2") (pin "16") (pinfunction "16_16") (pintype "passive"))
      (node (ref "JP3") (pin "17") (pinfunction "17_17") (pintype "passive"))
      (node (ref "L1-V1") (pin "8") (pinfunction "8_8") (pintype "passive"))
      (node (ref "SIDE1") (pin "4") (pinfunction "4_4") (pintype "passive"))
    )
    (net (code "282") (name "U2") (class "Default")
      (node (ref "IN3-4") (pin "14") (pinfunction "14_14") (pintype "passive"))
      (node (ref "JP4") (pin "17") (pinfunction "17_17") (pintype "passive"))
      (node (ref "L2-V2") (pin "8") (pinfunction "8_8") (pintype "passive"))
      (node (ref "SIDE2") (pin "34") (pinfunction "34_34") (pintype "passive"))
    )
    (net (code "283") (name "V1") (class "Default")
      (node (ref "IN3-4") (pin "1") (pinfunction "1_1") (pintype "passive"))
      (node (ref "JP3") (pin "18") (pinfunction "18_18") (pintype "passive"))
      (node (ref "L1-V1") (pin "9") (pinfunction "9_9") (pintype "passive"))
      (node (ref "SIDE1") (pin "2") (pinfunction "2_2") (pintype "passive"))
    )
    (net (code "284") (name "V2") (class "Default")
      (node (ref "IN3-4") (pin "16") (pinfunction "16_16") (pintype "passive"))
      (node (ref "JP4") (pin "18") (pinfunction "18_18") (pintype "passive"))
      (node (ref "L2-V2") (pin "9") (pinfunction "9_9") (pintype "passive"))
      (node (ref "SIDE2") (pin "32") (pinfunction "32_32") (pintype "passive"))
    )
    (net (code "285") (name "VCC") (class "Default")
      (node (ref "A2-K2") (pin "18") (pinfunction "18_18") (pintype "passive"))
      (node (ref "BYP1") (pin "1") (pinfunction "1_1") (pintype "passive"))
      (node (ref "BYP10") (pin "1") (pinfunction "1_1") (pintype "passive"))
      (node (ref "BYP2") (pin "1") (pinfunction "1_1") (pintype "passive"))
      (node (ref "BYP3") (pin "1") (pinfunction "1_1") (pintype "passive"))
      (node (ref "BYP4") (pin "1") (pinfunction "1_1") (pintype "passive"))
      (node (ref "BYP5") (pin "1") (pinfunction "1_1") (pintype "passive"))
      (node (ref "BYP6") (pin "1") (pinfunction "1_1") (pintype "passive"))
      (node (ref "BYP7") (pin "1") (pinfunction "1_1") (pintype "passive"))
      (node (ref "BYP8") (pin "1") (pinfunction "1_1") (pintype "passive"))
      (node (ref "BYP9") (pin "1") (pinfunction "1_1") (pintype "passive"))
      (node (ref "CORE-IO") (pin "12") (pinfunction "12_12") (pintype "passive"))
      (node (ref "CORE-IO") (pin "9") (pinfunction "9_9") (pintype "passive"))
      (node (ref "JP2") (pin "1") (pinfunction "1_1") (pintype "passive"))
      (node (ref "POWER") (pin "2") (pinfunction "2_2") (pintype "passive"))
    )
    (net (code "286") (name "unconnected-(CORE-IO-Pad1)") (class "Default")
      (node (ref "CORE-IO") (pin "1") (pinfunction "1_1") (pintype "passive"))
    )
    (net (code "287") (name "unconnected-(CORE-IO-Pad2)") (class "Default")
      (node (ref "CORE-IO") (pin "2") (pinfunction "2_2") (pintype "passive"))
    )
    (net (code "288") (name "unconnected-(CORE-IO-Pad3)") (class "Default")
      (node (ref "CORE-IO") (pin "3") (pinfunction "3_3") (pintype "passive"))
    )
    (net (code "289") (name "unconnected-(CORE-IO-Pad4)") (class "Default")
      (node (ref "CORE-IO") (pin "4") (pinfunction "4_4") (pintype "passive"))
    )
    (net (code "290") (name "unconnected-(CORE-IO-Pad5)") (class "Default")
      (node (ref "CORE-IO") (pin "5") (pinfunction "5_5") (pintype "passive"))
    )
    (net (code "291") (name "unconnected-(CORE-IO-Pad6)") (class "Default")
      (node (ref "CORE-IO") (pin "6") (pinfunction "6_6") (pintype "passive"))
    )
    (net (code "292") (name "unconnected-(CORE-IO-Pad7)") (class "Default")
      (node (ref "CORE-IO") (pin "7") (pinfunction "7_7") (pintype "passive"))
    )
    (net (code "293") (name "unconnected-(CORE-IO-Pad8)") (class "Default")
      (node (ref "CORE-IO") (pin "8") (pinfunction "8_8") (pintype "passive"))
    )
    (net (code "294") (name "unconnected-(CORE-IO-Pad13)") (class "Default")
      (node (ref "CORE-IO") (pin "13") (pinfunction "13_13") (pintype "passive"))
    )
    (net (code "295") (name "unconnected-(CORE-IO-Pad14)") (class "Default")
      (node (ref "CORE-IO") (pin "14") (pinfunction "14_14") (pintype "passive"))
    )
    (net (code "296") (name "unconnected-(CORE-IO-Pad15)") (class "Default")
      (node (ref "CORE-IO") (pin "15") (pinfunction "15_15") (pintype "passive"))
    )
    (net (code "297") (name "unconnected-(CORE-IO-Pad16)") (class "Default")
      (node (ref "CORE-IO") (pin "16") (pinfunction "16_16") (pintype "passive"))
    )
    (net (code "298") (name "unconnected-(CORE-IO-Pad17)") (class "Default")
      (node (ref "CORE-IO") (pin "17") (pinfunction "17_17") (pintype "passive"))
    )
    (net (code "299") (name "unconnected-(CORE-IO-Pad19)") (class "Default")
      (node (ref "CORE-IO") (pin "19") (pinfunction "19_19") (pintype "passive"))
    )
    (net (code "300") (name "unconnected-(IN5-6-Pad2)") (class "Default")
      (node (ref "IN5-6") (pin "2") (pinfunction "2_2") (pintype "passive"))
    )
    (net (code "301") (name "unconnected-(IN5-6-Pad3)") (class "Default")
      (node (ref "IN5-6") (pin "3") (pinfunction "3_3") (pintype "passive"))
    )
    (net (code "302") (name "unconnected-(IN5-6-Pad4)") (class "Default")
      (node (ref "IN5-6") (pin "4") (pinfunction "4_4") (pintype "passive"))
    )
    (net (code "303") (name "unconnected-(IN5-6-Pad5)") (class "Default")
      (node (ref "IN5-6") (pin "5") (pinfunction "5_5") (pintype "passive"))
    )
    (net (code "304") (name "unconnected-(IN5-6-Pad6)") (class "Default")
      (node (ref "IN5-6") (pin "6") (pinfunction "6_6") (pintype "passive"))
    )
    (net (code "305") (name "unconnected-(IN5-6-Pad7)") (class "Default")
      (node (ref "IN5-6") (pin "7") (pinfunction "7_7") (pintype "passive"))
    )
    (net (code "306") (name "unconnected-(IN5-6-Pad8)") (class "Default")
      (node (ref "IN5-6") (pin "8") (pinfunction "8_8") (pintype "passive"))
    )
    (net (code "307") (name "unconnected-(IN5-6-Pad9)") (class "Default")
      (node (ref "IN5-6") (pin "9") (pinfunction "9_9") (pintype "passive"))
    )
    (net (code "308") (name "unconnected-(IN5-6-Pad10)") (class "Default")
      (node (ref "IN5-6") (pin "10") (pinfunction "10_10") (pintype "passive"))
    )
    (net (code "309") (name "unconnected-(IN5-6-Pad11)") (class "Default")
      (node (ref "IN5-6") (pin "11") (pinfunction "11_11") (pintype "passive"))
    )
    (net (code "310") (name "unconnected-(IN5-6-Pad12)") (class "Default")
      (node (ref "IN5-6") (pin "12") (pinfunction "12_12") (pintype "passive"))
    )
    (net (code "311") (name "unconnected-(IN5-6-Pad13)") (class "Default")
      (node (ref "IN5-6") (pin "13") (pinfunction "13_13") (pintype "passive"))
    )
    (net (code "312") (name "unconnected-(IN5-6-Pad14)") (class "Default")
      (node (ref "IN5-6") (pin "14") (pinfunction "14_14") (pintype "passive"))
    )
    (net (code "313") (name "unconnected-(IN5-6-Pad15)") (class "Default")
      (node (ref "IN5-6") (pin "15") (pinfunction "15_15") (pintype "passive"))
    )
    (net (code "314") (name "unconnected-(IN5-6-Pad16)") (class "Default")
      (node (ref "IN5-6") (pin "16") (pinfunction "16_16") (pintype "passive"))
    )
    (net (code "315") (name "unconnected-(IN7-8-Pad1)") (class "Default")
      (node (ref "IN7-8") (pin "1") (pinfunction "1_1") (pintype "passive"))
    )
    (net (code "316") (name "unconnected-(IN7-8-Pad2)") (class "Default")
      (node (ref "IN7-8") (pin "2") (pinfunction "2_2") (pintype "passive"))
    )
    (net (code "317") (name "unconnected-(IN7-8-Pad3)") (class "Default")
      (node (ref "IN7-8") (pin "3") (pinfunction "3_3") (pintype "passive"))
    )
    (net (code "318") (name "unconnected-(IN7-8-Pad4)") (class "Default")
      (node (ref "IN7-8") (pin "4") (pinfunction "4_4") (pintype "passive"))
    )
    (net (code "319") (name "unconnected-(IN7-8-Pad5)") (class "Default")
      (node (ref "IN7-8") (pin "5") (pinfunction "5_5") (pintype "passive"))
    )
    (net (code "320") (name "unconnected-(IN7-8-Pad6)") (class "Default")
      (node (ref "IN7-8") (pin "6") (pinfunction "6_6") (pintype "passive"))
    )
    (net (code "321") (name "unconnected-(IN7-8-Pad7)") (class "Default")
      (node (ref "IN7-8") (pin "7") (pinfunction "7_7") (pintype "passive"))
    )
    (net (code "322") (name "unconnected-(IN7-8-Pad8)") (class "Default")
      (node (ref "IN7-8") (pin "8") (pinfunction "8_8") (pintype "passive"))
    )
    (net (code "323") (name "unconnected-(IN7-8-Pad9)") (class "Default")
      (node (ref "IN7-8") (pin "9") (pinfunction "9_9") (pintype "passive"))
    )
    (net (code "324") (name "unconnected-(IN7-8-Pad10)") (class "Default")
      (node (ref "IN7-8") (pin "10") (pinfunction "10_10") (pintype "passive"))
    )
    (net (code "325") (name "unconnected-(IN7-8-Pad11)") (class "Default")
      (node (ref "IN7-8") (pin "11") (pinfunction "11_11") (pintype "passive"))
    )
    (net (code "326") (name "unconnected-(IN7-8-Pad12)") (class "Default")
      (node (ref "IN7-8") (pin "12") (pinfunction "12_12") (pintype "passive"))
    )
    (net (code "327") (name "unconnected-(IN7-8-Pad13)") (class "Default")
      (node (ref "IN7-8") (pin "13") (pinfunction "13_13") (pintype "passive"))
    )
    (net (code "328") (name "unconnected-(IN7-8-Pad14)") (class "Default")
      (node (ref "IN7-8") (pin "14") (pinfunction "14_14") (pintype "passive"))
    )
    (net (code "329") (name "unconnected-(IN7-8-Pad15)") (class "Default")
      (node (ref "IN7-8") (pin "15") (pinfunction "15_15") (pintype "passive"))
    )
    (net (code "330") (name "unconnected-(IN7-8-Pad16)") (class "Default")
      (node (ref "IN7-8") (pin "16") (pinfunction "16_16") (pintype "passive"))
    )
    (net (code "331") (name "~{MR}") (class "Default")
      (node (ref "!MR") (pin "1") (pinfunction "1_1") (pintype "passive"))
      (node (ref "IC9") (pin "11") (pinfunction "O_11") (pintype "output"))
      (node (ref "IC9") (pin "9") (pinfunction "I0_9") (pintype "input"))
    )
  )
)
